# oresat-proto-card-Octavo.net
KiCad netlist of a schematic drawn in EAGLE
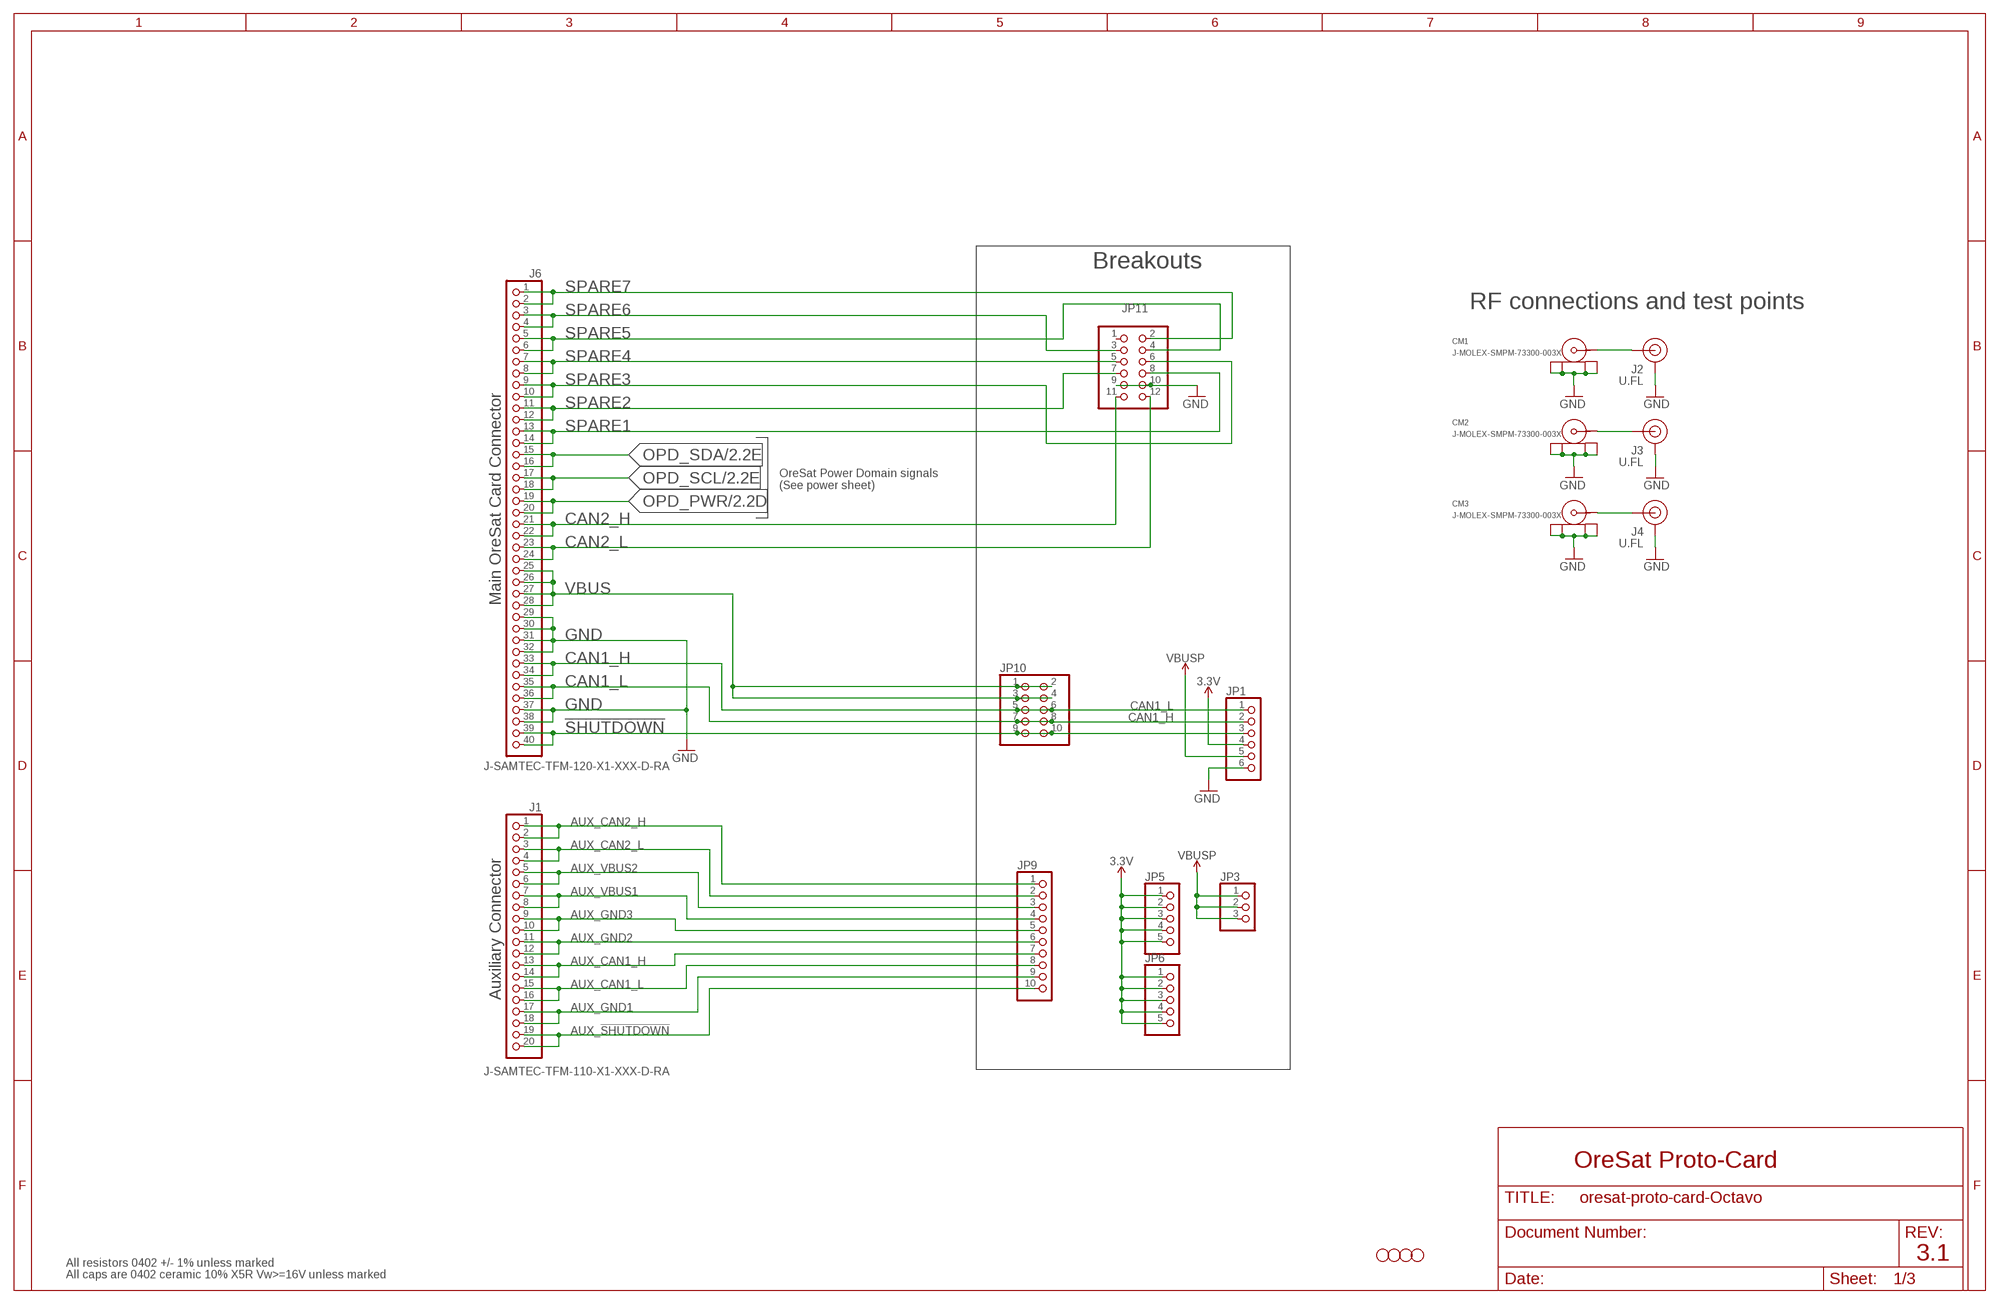
[diagram p0: schematic, sheet 1]
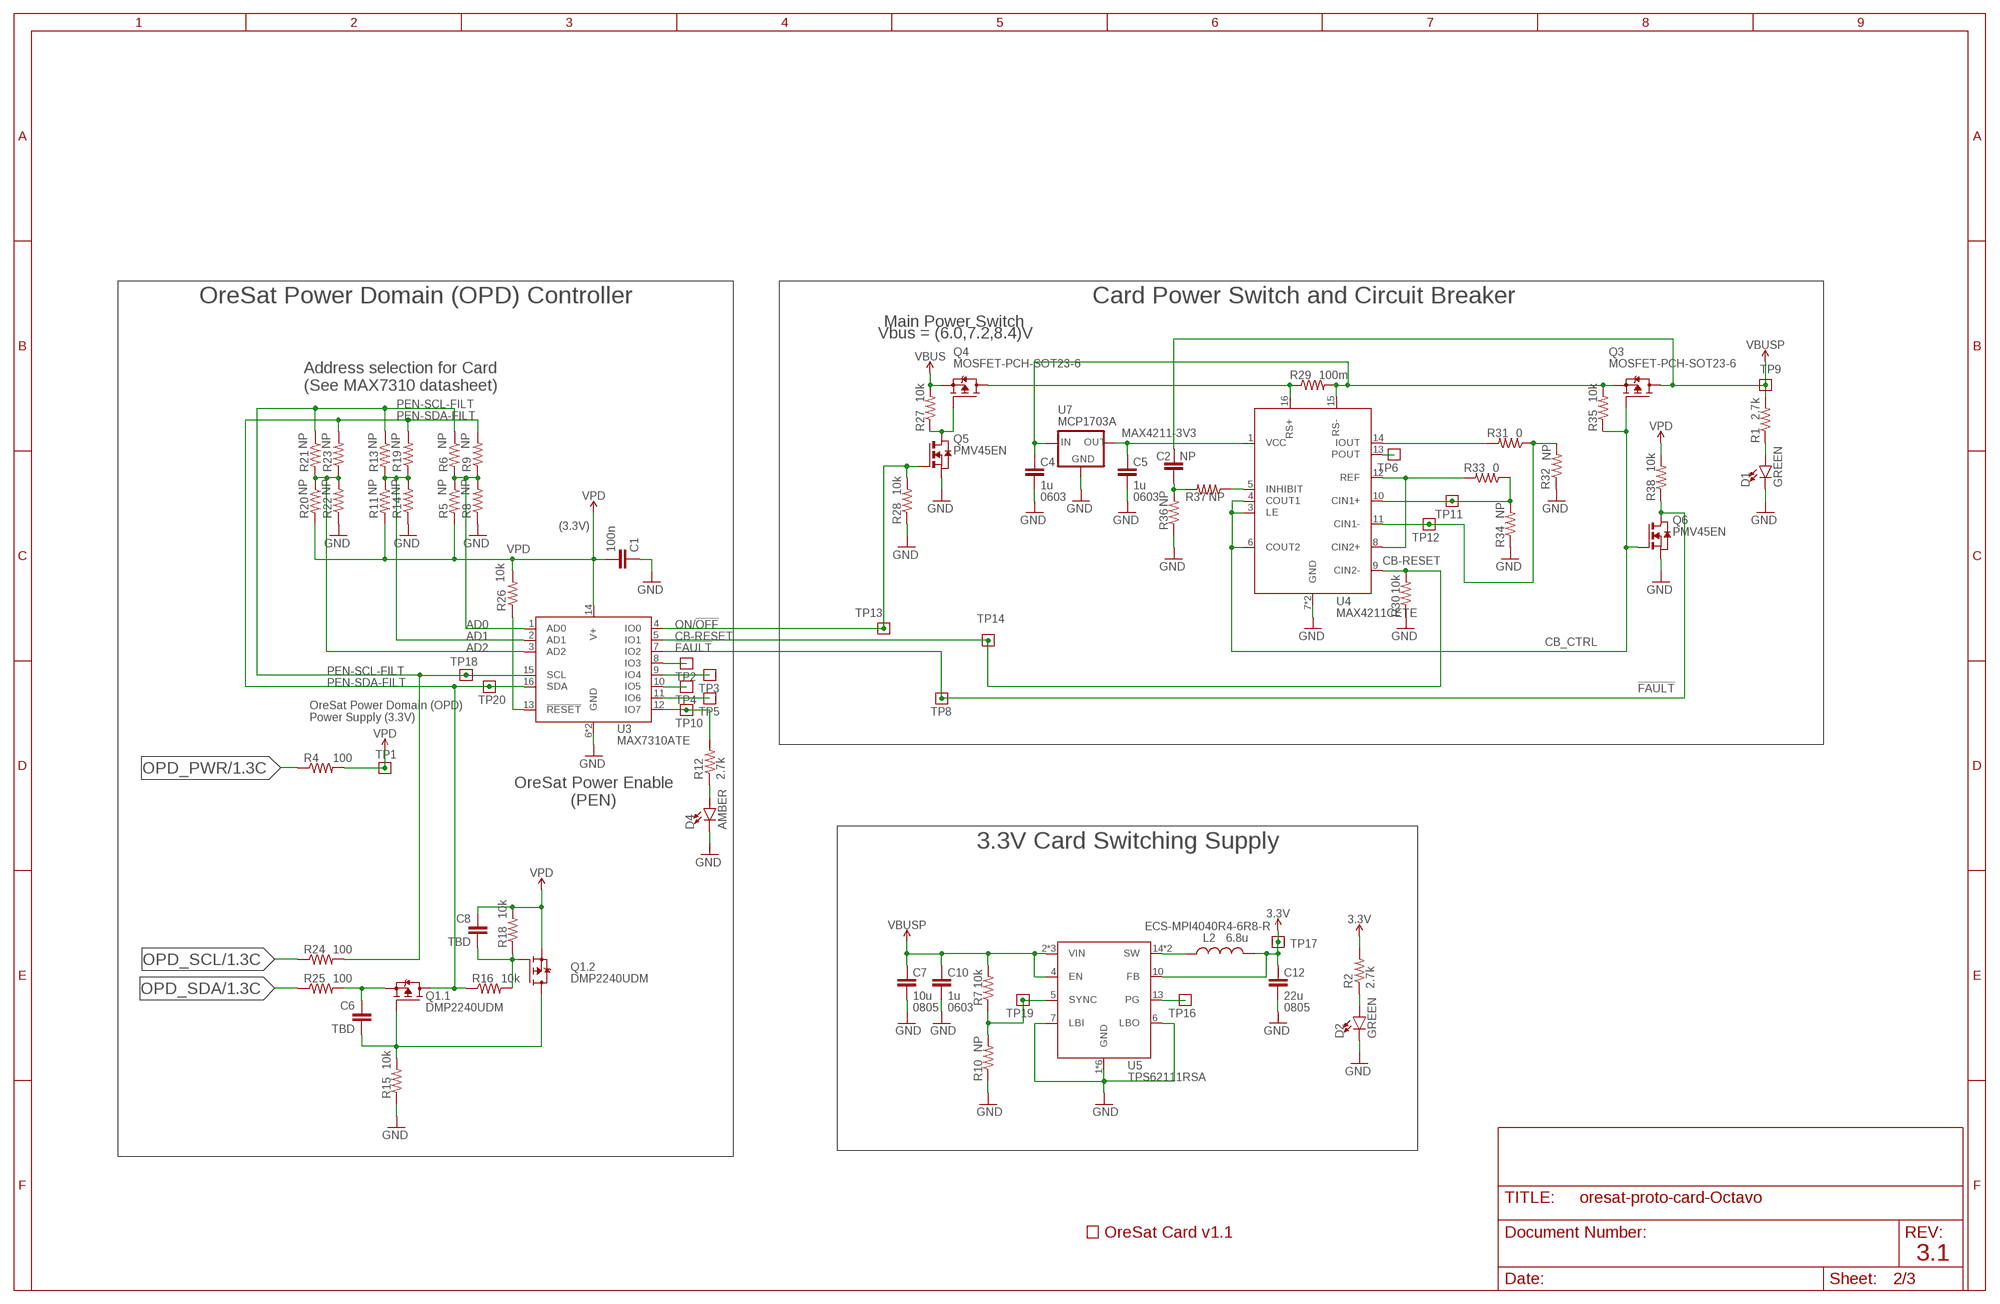
[diagram p1: schematic, sheet 2]
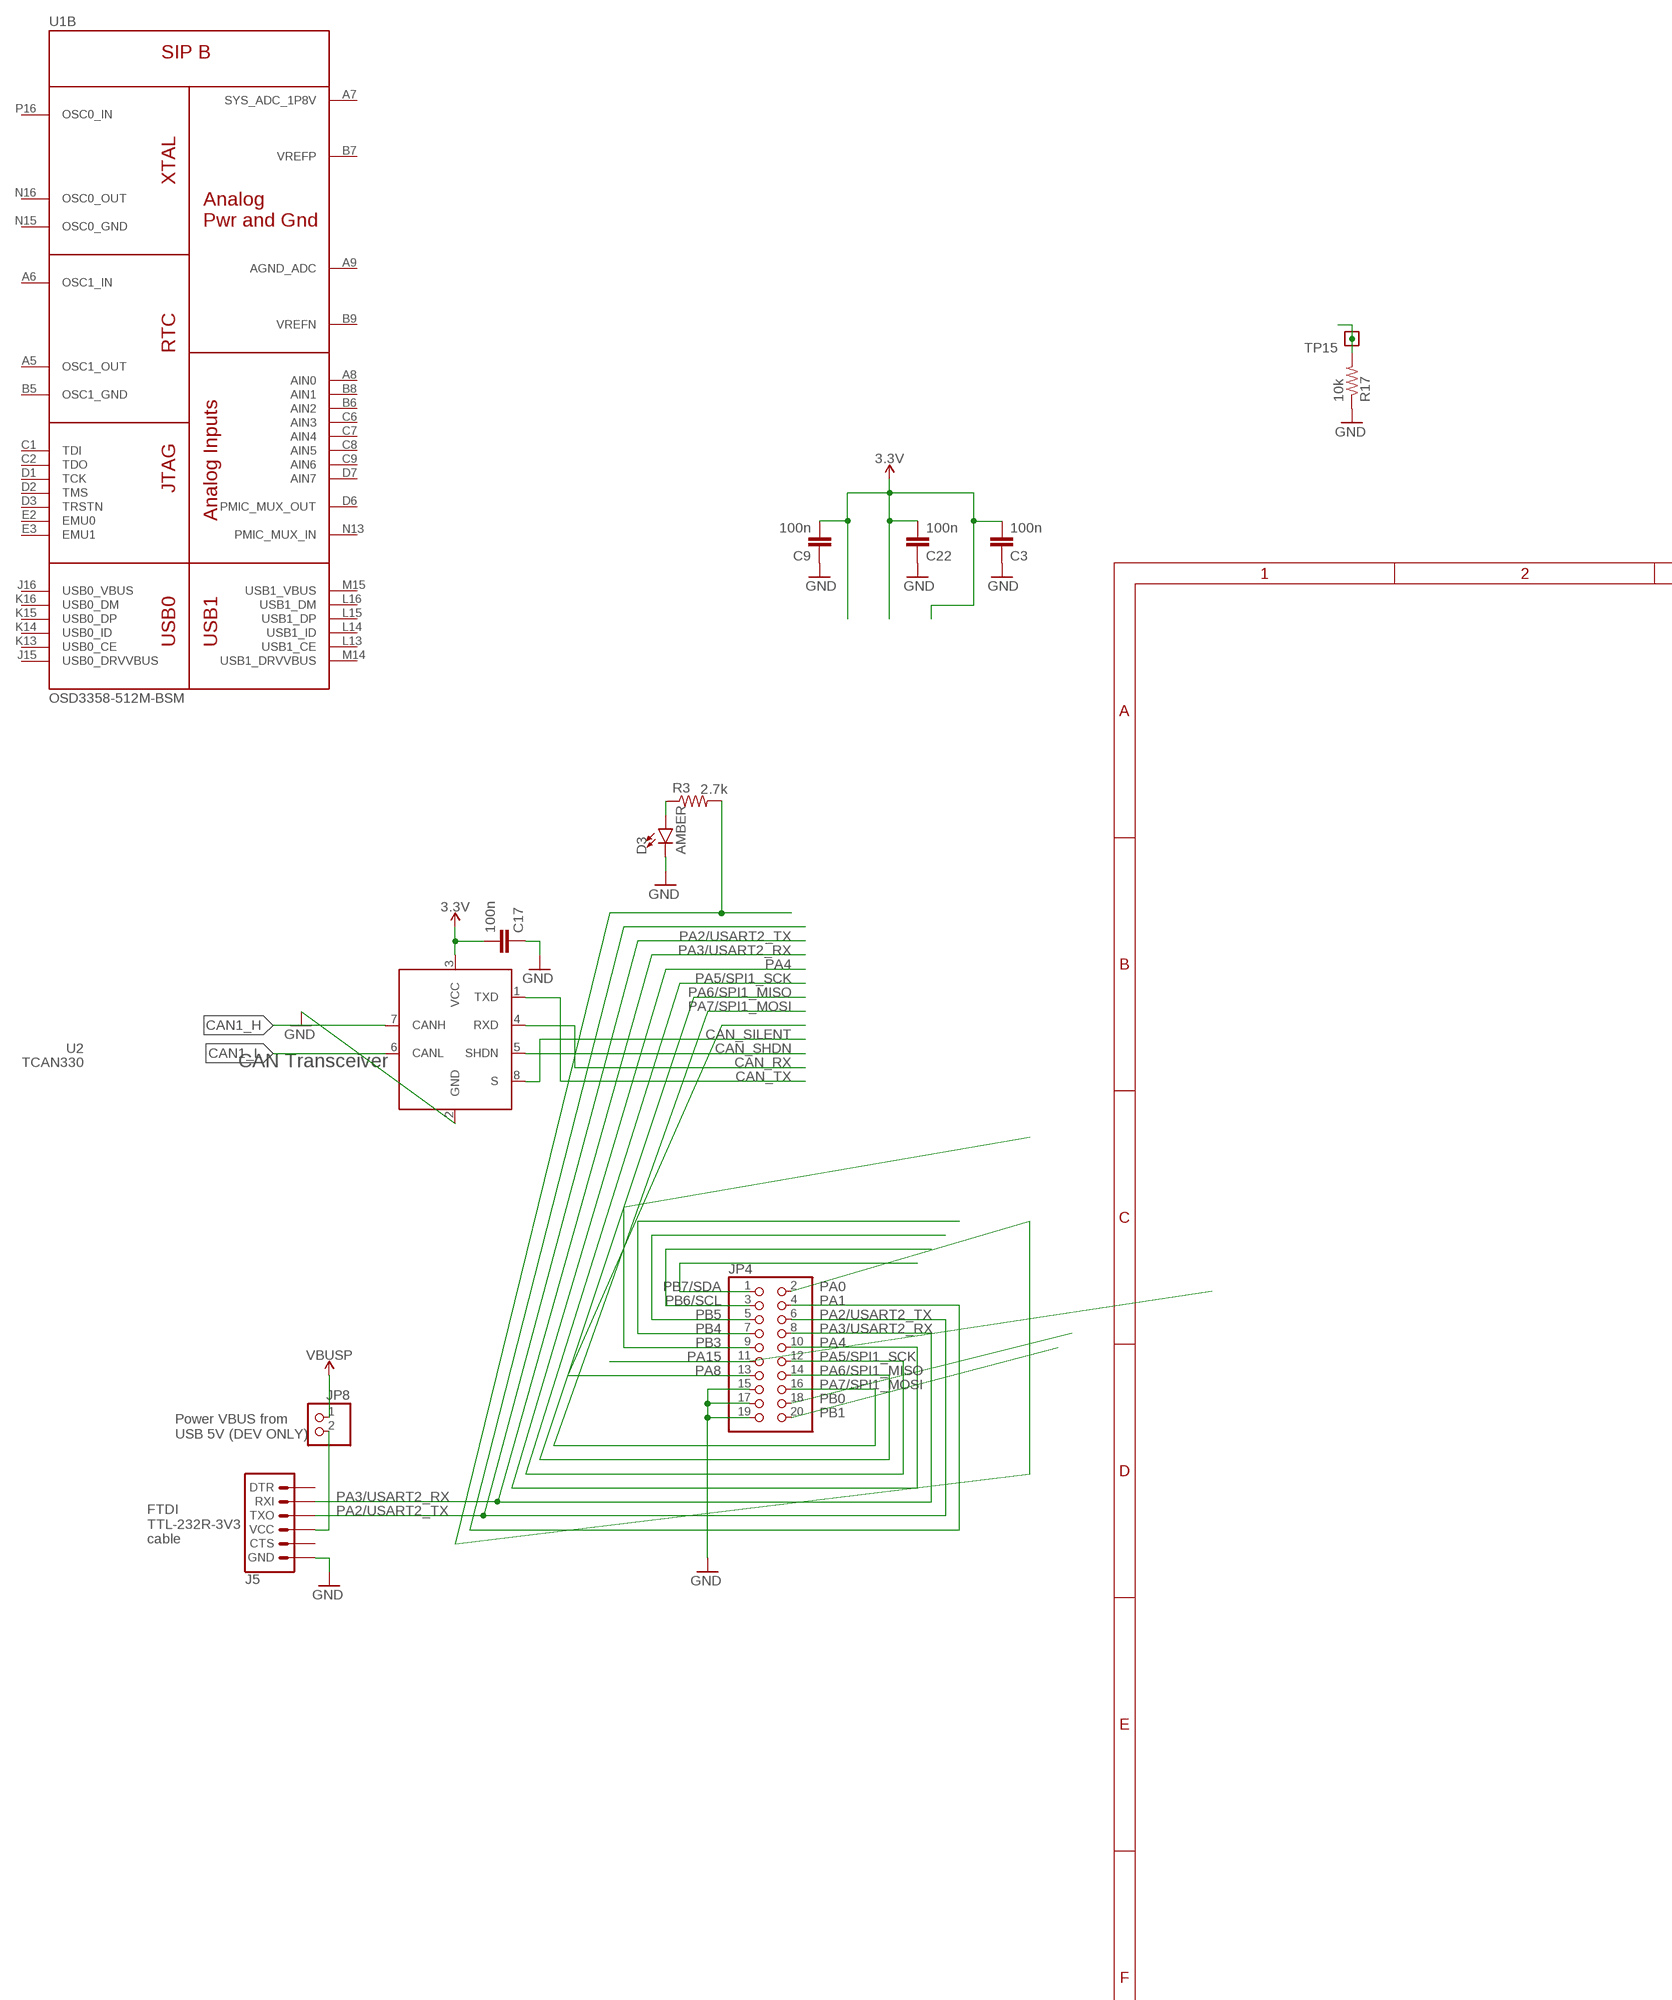
[diagram p2: schematic, sheet 3, part 1 of 2]
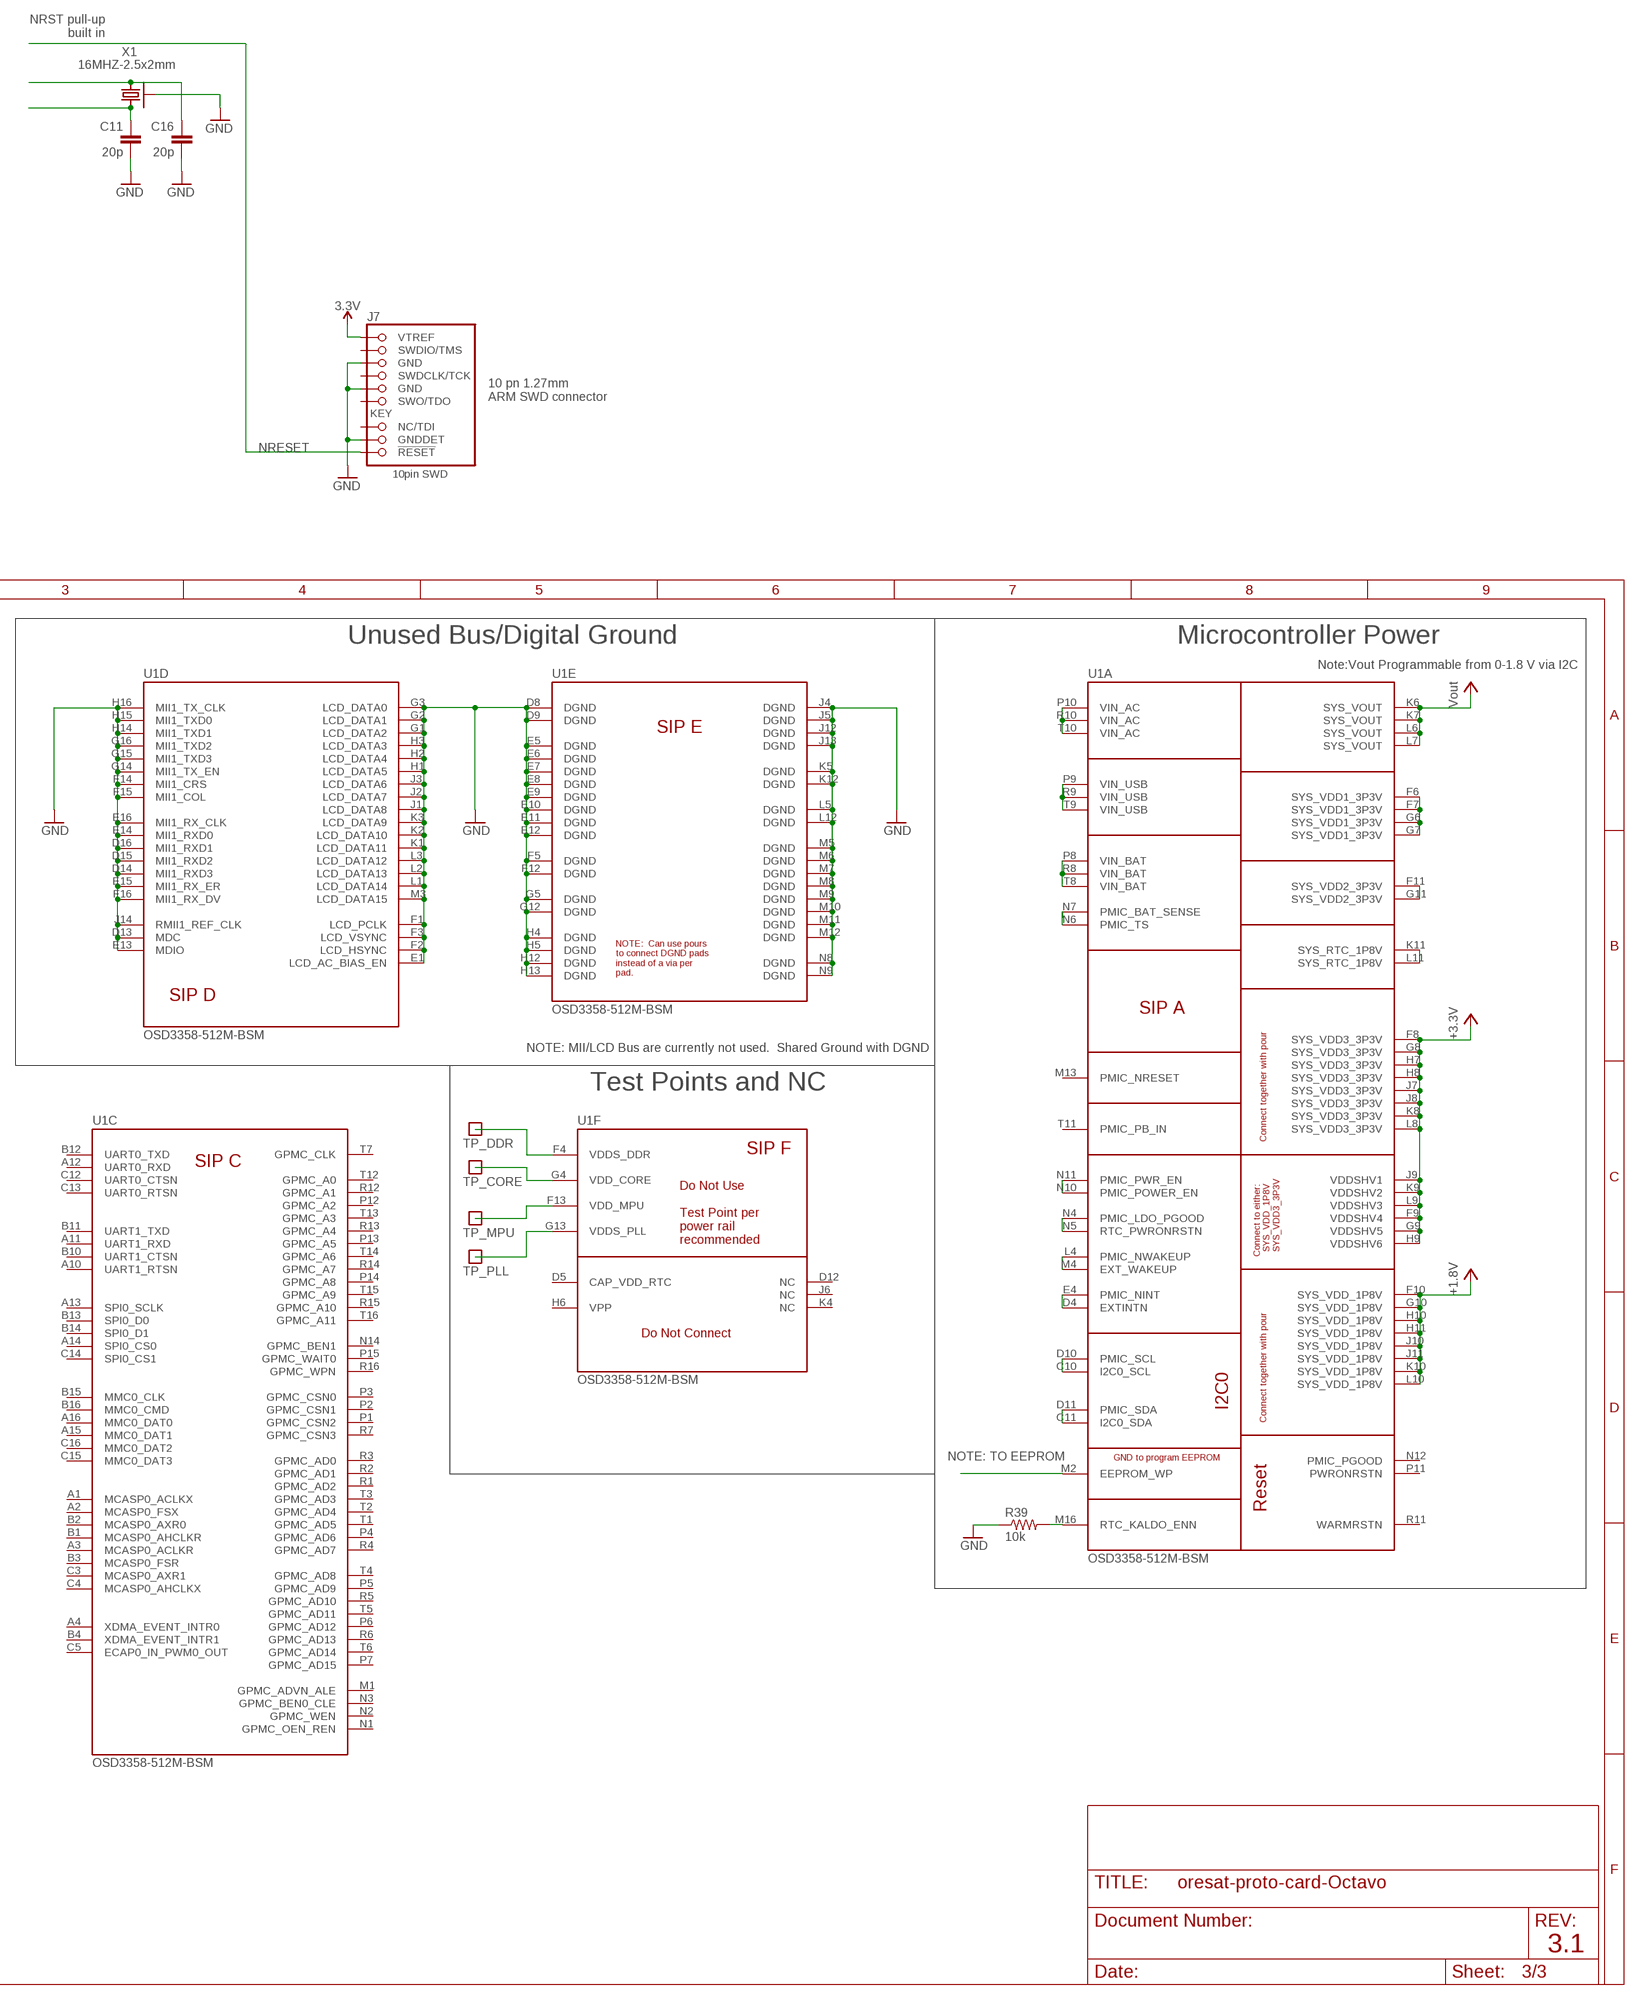
[diagram p3: schematic, sheet 3, part 2 of 2]

(export (version "E")
  (design (tool "Eeschema 10.0.6"))
  (components
    (comp (ref "C1")
      (value "100n")
      (footprint "eagle-import:.0402-B-NOSILK")
      (fields (field (name "MFR") "Samsung") (field (name "MPN") "CL05B104KO5NNNC"))
      (libsource (lib "eagle-import") (part "rcl_custom_C-EU0402-B-NOSILK"))
    )
    (comp (ref "C2")
      (value "NP")
      (footprint "eagle-import:.0402-B-NOSILK")
      (fields (field (name "MFR") "Samsung") (field (name "MPN") "CL05B104KO5NNNC"))
      (libsource (lib "eagle-import") (part "rcl_custom_C-EU0402-B-NOSILK"))
    )
    (comp (ref "C4")
      (value "1u")
      (footprint "eagle-import:.0603-B-NOSILK")
      (fields (field (name "MFR") "Samsung") (field (name "MPN") "CL05B104KO5NNNC"))
      (libsource (lib "eagle-import") (part "C-EU0603-B-NOSILK"))
    )
    (comp (ref "C5")
      (value "1u")
      (footprint "eagle-import:.0603-B-NOSILK")
      (fields (field (name "MFR") "Samsung") (field (name "MPN") "CL05B104KO5NNNC"))
      (libsource (lib "eagle-import") (part "C-EU0603-B-NOSILK"))
    )
    (comp (ref "C6")
      (value "TBD")
      (footprint "eagle-import:.0402-B-NOSILK")
      (fields (field (name "MFR") "Samsung") (field (name "MPN") "CL05B104KO5NNNC"))
      (libsource (lib "eagle-import") (part "rcl_custom_C-EU0402-B-NOSILK"))
    )
    (comp (ref "C7")
      (value "10u")
      (footprint "eagle-import:.0805-B-NOSILK")
      (libsource (lib "eagle-import") (part "C-EU0805-B-NOSILK"))
    )
    (comp (ref "C8")
      (value "TBD")
      (footprint "eagle-import:.0402-B-NOSILK")
      (fields (field (name "MFR") "Samsung") (field (name "MPN") "CL05B104KO5NNNC"))
      (libsource (lib "eagle-import") (part "rcl_custom_C-EU0402-B-NOSILK"))
    )
    (comp (ref "C10")
      (value "1u")
      (footprint "eagle-import:.0603-B-NOSILK")
      (fields (field (name "MFR") "Samsung") (field (name "MPN") "CL05B104KO5NNNC"))
      (libsource (lib "eagle-import") (part "C-EU0603-B-NOSILK"))
    )
    (comp (ref "C12")
      (value "22u")
      (footprint "eagle-import:.0805-B-NOSILK")
      (libsource (lib "eagle-import") (part "C-EU0805-B-NOSILK"))
    )
    (comp (ref "D1")
      (value "GREEN")
      (footprint "eagle-import:LED-0603")
      (libsource (lib "eagle-import") (part "LED-GREEN0603"))
    )
    (comp (ref "D2")
      (value "GREEN")
      (footprint "eagle-import:LED-0603")
      (libsource (lib "eagle-import") (part "LED-GREEN0603"))
    )
    (comp (ref "D4")
      (value "AMBER")
      (footprint "eagle-import:LED-0603")
      (libsource (lib "eagle-import") (part "LED-GREEN0603"))
    )
    (comp (ref "L2")
      (value "6.8u")
      (footprint "eagle-import:ECS-MPI4040")
      (fields (field (name "MFR") "ECS") (field (name "MPN") "ECS-MPI4040R4-6R8-R"))
      (libsource (lib "eagle-import") (part "L-ECS-MPI4040"))
    )
    (comp (ref "Q1")
      (value "DMP2240UDM")
      (footprint "eagle-import:SOT23-6")
      (fields (field (name "MFR") "Diodes Inc") (field (name "MPN") "DMP2240UDM"))
      (libsource (lib "eagle-import") (part "Q-MOSFET-PCH-dual-SOT23-6_MOSFET-PCH-SOT23-6"))
    )
    (comp (ref "Q3")
      (value "MOSFET-PCH-SOT23-6")
      (footprint "eagle-import:SOT23-6")
      (fields (field (name "MFR") "Diodes Inc") (field (name "MPN") "DMP3050LVT-7"))
      (libsource (lib "eagle-import") (part "MOSFET-PCH-SOT23-6"))
    )
    (comp (ref "Q4")
      (value "MOSFET-PCH-SOT23-6")
      (footprint "eagle-import:SOT23-6")
      (fields (field (name "MFR") "Diodes Inc") (field (name "MPN") "DMP3050LVT-7"))
      (libsource (lib "eagle-import") (part "MOSFET-PCH-SOT23-6"))
    )
    (comp (ref "Q5")
      (value "PMV45EN")
      (footprint "eagle-import:SOT23")
      (libsource (lib "eagle-import") (part "PMV45EN"))
    )
    (comp (ref "Q6")
      (value "PMV45EN")
      (footprint "eagle-import:SOT23")
      (libsource (lib "eagle-import") (part "PMV45EN"))
    )
    (comp (ref "R1")
      (value "2.7k")
      (footprint "eagle-import:.0402-B-NOSILK")
      (fields (field (name "MFR") "Samsung") (field (name "MPN") "RC1005F6653CS"))
      (libsource (lib "eagle-import") (part "R-US_0402-B-NOSILK"))
    )
    (comp (ref "R2")
      (value "2.7k")
      (footprint "eagle-import:.0402-B-NOSILK")
      (fields (field (name "MFR") "Samsung") (field (name "MPN") "RC1005F6653CS"))
      (libsource (lib "eagle-import") (part "R-US_0402-B-NOSILK"))
    )
    (comp (ref "R4")
      (value "100")
      (footprint "eagle-import:.0402-B-NOSILK")
      (fields (field (name "MFR") "Samsung") (field (name "MPN") "RC1005F6653CS"))
      (libsource (lib "eagle-import") (part "R-US_0402-B-NOSILK"))
    )
    (comp (ref "R5")
      (value "NP")
      (footprint "eagle-import:.0402-B-NOSILK")
      (fields (field (name "MFR") "Samsung") (field (name "MPN") "RC1005F6653CS"))
      (libsource (lib "eagle-import") (part "R-US_0402-B-NOSILK"))
    )
    (comp (ref "R6")
      (value "NP")
      (footprint "eagle-import:.0402-B-NOSILK")
      (fields (field (name "MFR") "Samsung") (field (name "MPN") "RC1005F6653CS"))
      (libsource (lib "eagle-import") (part "R-US_0402-B-NOSILK"))
    )
    (comp (ref "R7")
      (value "10k")
      (footprint "eagle-import:.0402-B-NOSILK")
      (fields (field (name "MFR") "Samsung") (field (name "MPN") "RC1005F6653CS"))
      (libsource (lib "eagle-import") (part "R-US_0402-B-NOSILK"))
    )
    (comp (ref "R8")
      (value "NP")
      (footprint "eagle-import:.0402-B-NOSILK")
      (fields (field (name "MFR") "Samsung") (field (name "MPN") "RC1005F6653CS"))
      (libsource (lib "eagle-import") (part "R-US_0402-B-NOSILK"))
    )
    (comp (ref "R9")
      (value "NP")
      (footprint "eagle-import:.0402-B-NOSILK")
      (fields (field (name "MFR") "Samsung") (field (name "MPN") "RC1005F6653CS"))
      (libsource (lib "eagle-import") (part "R-US_0402-B-NOSILK"))
    )
    (comp (ref "R10")
      (value "NP")
      (footprint "eagle-import:.0402-B-NOSILK")
      (fields (field (name "MFR") "Samsung") (field (name "MPN") "RC1005F6653CS"))
      (libsource (lib "eagle-import") (part "R-US_0402-B-NOSILK"))
    )
    (comp (ref "R11")
      (value "NP")
      (footprint "eagle-import:.0402-B-NOSILK")
      (fields (field (name "MFR") "Samsung") (field (name "MPN") "RC1005F6653CS"))
      (libsource (lib "eagle-import") (part "R-US_0402-B-NOSILK"))
    )
    (comp (ref "R12")
      (value "2.7k")
      (footprint "eagle-import:.0402-B-NOSILK")
      (fields (field (name "MFR") "Samsung") (field (name "MPN") "RC1005F6653CS"))
      (libsource (lib "eagle-import") (part "R-US_0402-B-NOSILK"))
    )
    (comp (ref "R13")
      (value "NP")
      (footprint "eagle-import:.0402-B-NOSILK")
      (fields (field (name "MFR") "Samsung") (field (name "MPN") "RC1005F6653CS"))
      (libsource (lib "eagle-import") (part "R-US_0402-B-NOSILK"))
    )
    (comp (ref "R14")
      (value "NP")
      (footprint "eagle-import:.0402-B-NOSILK")
      (fields (field (name "MFR") "Samsung") (field (name "MPN") "RC1005F6653CS"))
      (libsource (lib "eagle-import") (part "R-US_0402-B-NOSILK"))
    )
    (comp (ref "R15")
      (value "10k")
      (footprint "eagle-import:.0402-B-NOSILK")
      (fields (field (name "MFR") "Samsung") (field (name "MPN") "RC1005F6653CS"))
      (libsource (lib "eagle-import") (part "R-US_0402-B-NOSILK"))
    )
    (comp (ref "R16")
      (value "10k")
      (footprint "eagle-import:.0402-B-NOSILK")
      (fields (field (name "MFR") "Samsung") (field (name "MPN") "RC1005F6653CS"))
      (libsource (lib "eagle-import") (part "R-US_0402-B-NOSILK"))
    )
    (comp (ref "R18")
      (value "10k")
      (footprint "eagle-import:.0402-B-NOSILK")
      (fields (field (name "MFR") "Samsung") (field (name "MPN") "RC1005F6653CS"))
      (libsource (lib "eagle-import") (part "R-US_0402-B-NOSILK"))
    )
    (comp (ref "R19")
      (value "NP")
      (footprint "eagle-import:.0402-B-NOSILK")
      (fields (field (name "MFR") "Samsung") (field (name "MPN") "RC1005F6653CS"))
      (libsource (lib "eagle-import") (part "R-US_0402-B-NOSILK"))
    )
    (comp (ref "R20")
      (value "NP")
      (footprint "eagle-import:.0402-B-NOSILK")
      (fields (field (name "MFR") "Samsung") (field (name "MPN") "RC1005F6653CS"))
      (libsource (lib "eagle-import") (part "R-US_0402-B-NOSILK"))
    )
    (comp (ref "R21")
      (value "NP")
      (footprint "eagle-import:.0402-B-NOSILK")
      (fields (field (name "MFR") "Samsung") (field (name "MPN") "RC1005F6653CS"))
      (libsource (lib "eagle-import") (part "R-US_0402-B-NOSILK"))
    )
    (comp (ref "R22")
      (value "NP")
      (footprint "eagle-import:.0402-B-NOSILK")
      (fields (field (name "MFR") "Samsung") (field (name "MPN") "RC1005F6653CS"))
      (libsource (lib "eagle-import") (part "R-US_0402-B-NOSILK"))
    )
    (comp (ref "R23")
      (value "NP")
      (footprint "eagle-import:.0402-B-NOSILK")
      (fields (field (name "MFR") "Samsung") (field (name "MPN") "RC1005F6653CS"))
      (libsource (lib "eagle-import") (part "R-US_0402-B-NOSILK"))
    )
    (comp (ref "R24")
      (value "100")
      (footprint "eagle-import:.0402-B-NOSILK")
      (fields (field (name "MFR") "Samsung") (field (name "MPN") "RC1005F6653CS"))
      (libsource (lib "eagle-import") (part "R-US_0402-B-NOSILK"))
    )
    (comp (ref "R25")
      (value "100")
      (footprint "eagle-import:.0402-B-NOSILK")
      (fields (field (name "MFR") "Samsung") (field (name "MPN") "RC1005F6653CS"))
      (libsource (lib "eagle-import") (part "R-US_0402-B-NOSILK"))
    )
    (comp (ref "R26")
      (value "10k")
      (footprint "eagle-import:.0402-B-NOSILK")
      (fields (field (name "MFR") "Samsung") (field (name "MPN") "RC1005F6653CS"))
      (libsource (lib "eagle-import") (part "R-US_0402-B-NOSILK"))
    )
    (comp (ref "R27")
      (value "10k")
      (footprint "eagle-import:.0402-B-NOSILK")
      (fields (field (name "MFR") "Samsung") (field (name "MPN") "RC1005F6653CS"))
      (libsource (lib "eagle-import") (part "R-US_0402-B-NOSILK"))
    )
    (comp (ref "R28")
      (value "10k")
      (footprint "eagle-import:.0402-B-NOSILK")
      (fields (field (name "MFR") "Samsung") (field (name "MPN") "RC1005F6653CS"))
      (libsource (lib "eagle-import") (part "R-US_0402-B-NOSILK"))
    )
    (comp (ref "R29")
      (value "100m")
      (footprint "eagle-import:R1206")
      (libsource (lib "eagle-import") (part "R-US_R1206"))
    )
    (comp (ref "R30")
      (value "10k")
      (footprint "eagle-import:.0402-B-NOSILK")
      (fields (field (name "MFR") "Samsung") (field (name "MPN") "RC1005F6653CS"))
      (libsource (lib "eagle-import") (part "R-US_0402-B-NOSILK"))
    )
    (comp (ref "R31")
      (value "0")
      (footprint "eagle-import:.0402-B-NOSILK")
      (fields (field (name "MFR") "Samsung") (field (name "MPN") "RC1005F6653CS"))
      (libsource (lib "eagle-import") (part "R-US_0402-B-NOSILK"))
    )
    (comp (ref "R32")
      (value "NP")
      (footprint "eagle-import:.0402-B-NOSILK")
      (fields (field (name "MFR") "Samsung") (field (name "MPN") "RC1005F6653CS"))
      (libsource (lib "eagle-import") (part "R-US_0402-B-NOSILK"))
    )
    (comp (ref "R33")
      (value "0")
      (footprint "eagle-import:.0402-B-NOSILK")
      (fields (field (name "MFR") "Samsung") (field (name "MPN") "RC1005F6653CS"))
      (libsource (lib "eagle-import") (part "R-US_0402-B-NOSILK"))
    )
    (comp (ref "R34")
      (value "NP")
      (footprint "eagle-import:.0402-B-NOSILK")
      (fields (field (name "MFR") "Samsung") (field (name "MPN") "RC1005F6653CS"))
      (libsource (lib "eagle-import") (part "R-US_0402-B-NOSILK"))
    )
    (comp (ref "R35")
      (value "10k")
      (footprint "eagle-import:.0402-B-NOSILK")
      (fields (field (name "MFR") "Samsung") (field (name "MPN") "RC1005F6653CS"))
      (libsource (lib "eagle-import") (part "R-US_0402-B-NOSILK"))
    )
    (comp (ref "R36")
      (value "NP")
      (footprint "eagle-import:.0402-B-NOSILK")
      (fields (field (name "MFR") "Samsung") (field (name "MPN") "RC1005F6653CS"))
      (libsource (lib "eagle-import") (part "R-US_0402-B-NOSILK"))
    )
    (comp (ref "R37")
      (value "NP")
      (footprint "eagle-import:.0402-B-NOSILK")
      (fields (field (name "MFR") "Samsung") (field (name "MPN") "RC1005F6653CS"))
      (libsource (lib "eagle-import") (part "R-US_0402-B-NOSILK"))
    )
    (comp (ref "R38")
      (value "10k")
      (footprint "eagle-import:.0402-B-NOSILK")
      (fields (field (name "MFR") "Samsung") (field (name "MPN") "RC1005F6653CS"))
      (libsource (lib "eagle-import") (part "R-US_0402-B-NOSILK"))
    )
    (comp (ref "TP1")
      (value "TEST-POINT")
      (footprint "eagle-import:2MM-TEST-POINT")
      (libsource (lib "eagle-import") (part "TEST-POINT"))
    )
    (comp (ref "TP2")
      (value "TEST-POINT")
      (footprint "eagle-import:2MM-TEST-POINT")
      (libsource (lib "eagle-import") (part "TEST-POINT"))
    )
    (comp (ref "TP3")
      (value "TEST-POINT")
      (footprint "eagle-import:2MM-TEST-POINT")
      (libsource (lib "eagle-import") (part "TEST-POINT"))
    )
    (comp (ref "TP4")
      (value "TEST-POINT")
      (footprint "eagle-import:2MM-TEST-POINT")
      (libsource (lib "eagle-import") (part "TEST-POINT"))
    )
    (comp (ref "TP5")
      (value "TEST-POINT")
      (footprint "eagle-import:2MM-TEST-POINT")
      (libsource (lib "eagle-import") (part "TEST-POINT"))
    )
    (comp (ref "TP6")
      (value "TEST-POINT")
      (footprint "eagle-import:2MM-TEST-POINT")
      (libsource (lib "eagle-import") (part "TEST-POINT"))
    )
    (comp (ref "TP8")
      (value "TEST-POINT")
      (footprint "eagle-import:2MM-TEST-POINT")
      (libsource (lib "eagle-import") (part "TEST-POINT"))
    )
    (comp (ref "TP9")
      (value "TEST-POINT")
      (footprint "eagle-import:2MM-TEST-POINT")
      (libsource (lib "eagle-import") (part "TEST-POINT"))
    )
    (comp (ref "TP10")
      (value "TEST-POINT")
      (footprint "eagle-import:2MM-TEST-POINT")
      (libsource (lib "eagle-import") (part "TEST-POINT"))
    )
    (comp (ref "TP11")
      (value "TEST-POINT")
      (footprint "eagle-import:2MM-TEST-POINT")
      (libsource (lib "eagle-import") (part "TEST-POINT"))
    )
    (comp (ref "TP12")
      (value "TEST-POINT")
      (footprint "eagle-import:2MM-TEST-POINT")
      (libsource (lib "eagle-import") (part "TEST-POINT"))
    )
    (comp (ref "TP13")
      (value "TEST-POINT")
      (footprint "eagle-import:2MM-TEST-POINT")
      (libsource (lib "eagle-import") (part "TEST-POINT"))
    )
    (comp (ref "TP14")
      (value "TEST-POINT")
      (footprint "eagle-import:2MM-TEST-POINT")
      (libsource (lib "eagle-import") (part "TEST-POINT"))
    )
    (comp (ref "TP16")
      (value "TEST-POINT")
      (footprint "eagle-import:2MM-TEST-POINT")
      (libsource (lib "eagle-import") (part "TEST-POINT"))
    )
    (comp (ref "TP17")
      (value "TEST-POINT")
      (footprint "eagle-import:2MM-TEST-POINT")
      (libsource (lib "eagle-import") (part "TEST-POINT"))
    )
    (comp (ref "TP18")
      (value "TEST-POINT")
      (footprint "eagle-import:2MM-TEST-POINT")
      (libsource (lib "eagle-import") (part "TEST-POINT"))
    )
    (comp (ref "TP19")
      (value "TEST-POINT")
      (footprint "eagle-import:2MM-TEST-POINT")
      (libsource (lib "eagle-import") (part "TEST-POINT"))
    )
    (comp (ref "TP20")
      (value "TEST-POINT")
      (footprint "eagle-import:2MM-TEST-POINT")
      (libsource (lib "eagle-import") (part "TEST-POINT"))
    )
    (comp (ref "U$1")
      (value "ORESAT-CARD-V1.1-3XRF")
      (footprint "eagle-import:ORESAT-CARD-V1.1-3XRF")
      (libsource (lib "eagle-import") (part "ORESAT-CARD-V1.1-3XRF"))
    )
    (comp (ref "U3")
      (value "MAX7310ATE")
      (footprint "eagle-import:QFN65P400X400X80-17T210")
      (fields (field (name "MFR") "Maxim"))
      (libsource (lib "eagle-import") (part "MAX7310"))
    )
    (comp (ref "U4")
      (value "MAX4211CETE")
      (footprint "eagle-import:QFN65P400X400X80-17T210")
      (fields (field (name "MFR") "Maxim"))
      (libsource (lib "eagle-import") (part "MAX4211"))
    )
    (comp (ref "U5")
      (value "TPS62111RSA")
      (footprint "eagle-import:S-PVQFN-16")
      (fields (field (name "MFR") "TI"))
      (libsource (lib "eagle-import") (part "TPS6211X"))
    )
    (comp (ref "U7")
      (value "MCP1703A")
      (footprint "eagle-import:SOT23")
      (fields (field (name "MFR") "Microchip") (field (name "MPN") "MCP1703AT-3302E/CB"))
      (libsource (lib "eagle-import") (part "XC63FPM"))
    )
    (comp (ref "C3")
      (value "100n")
      (footprint "eagle-import:.0402-B-NOSILK")
      (fields (field (name "MFR") "Samsung") (field (name "MPN") "CL05B104KO5NNNC"))
      (libsource (lib "eagle-import") (part "rcl_custom_C-EU0402-B-NOSILK"))
    )
    (comp (ref "C9")
      (value "100n")
      (footprint "eagle-import:.0402-B-NOSILK")
      (fields (field (name "MFR") "Samsung") (field (name "MPN") "CL05B104KO5NNNC"))
      (libsource (lib "eagle-import") (part "rcl_custom_C-EU0402-B-NOSILK"))
    )
    (comp (ref "C11")
      (value "20p")
      (footprint "eagle-import:.0402-B-NOSILK")
      (fields (field (name "MFR") "Samsung") (field (name "MPN") "CL05C200JB51PNC"))
      (libsource (lib "eagle-import") (part "rcl_custom_C-EU0402-B-NOSILK"))
    )
    (comp (ref "C16")
      (value "20p")
      (footprint "eagle-import:.0402-B-NOSILK")
      (fields (field (name "MFR") "Samsung") (field (name "MPN") "CL05C200JB51PNC"))
      (libsource (lib "eagle-import") (part "rcl_custom_C-EU0402-B-NOSILK"))
    )
    (comp (ref "C17")
      (value "100n")
      (footprint "eagle-import:.0402-B-NOSILK")
      (fields (field (name "MFR") "Samsung") (field (name "MPN") "CL05B104KO5NNNC"))
      (libsource (lib "eagle-import") (part "rcl_custom_C-EU0402-B-NOSILK"))
    )
    (comp (ref "C22")
      (value "100n")
      (footprint "eagle-import:.0402-B-NOSILK")
      (fields (field (name "MFR") "Samsung") (field (name "MPN") "CL05B104KO5NNNC"))
      (libsource (lib "eagle-import") (part "rcl_custom_C-EU0402-B-NOSILK"))
    )
    (comp (ref "D3")
      (value "AMBER")
      (footprint "eagle-import:LED-0603")
      (libsource (lib "eagle-import") (part "LED-GREEN0603"))
    )
    (comp (ref "J5")
      (value "6_PIN_SERIAL_TARGETSILK")
      (footprint "eagle-import:6_PIN_SERIAL_TARGET_SIDE_W_SILK")
      (libsource (lib "eagle-import") (part "6_PIN_SERIAL_TARGETSILK"))
    )
    (comp (ref "J7")
      (value "FTSH-105-XX-X-DV-K")
      (footprint "eagle-import:CON10_2X5_DUK_FTSH")
      (fields (field (name "MFR") "Samtec") (field (name "MPN") "FTSH-105-01-F-DV-K"))
      (libsource (lib "eagle-import") (part "FTSH-105-XX-X-DV-K"))
    )
    (comp (ref "JP4")
      (value "PINHD-2X10")
      (footprint "eagle-import:2X10")
      (libsource (lib "eagle-import") (part "PINHD-2X10"))
    )
    (comp (ref "JP8")
      (value "PINHD-1X2")
      (footprint "eagle-import:1X02")
      (libsource (lib "eagle-import") (part "PINHD-1X2"))
    )
    (comp (ref "R3")
      (value "2.7k")
      (footprint "eagle-import:.0402-B-NOSILK")
      (fields (field (name "MFR") "Samsung") (field (name "MPN") "RC1005F6653CS"))
      (libsource (lib "eagle-import") (part "R-US_0402-B-NOSILK"))
    )
    (comp (ref "R17")
      (value "10k")
      (footprint "eagle-import:.0402-B-NOSILK")
      (fields (field (name "MFR") "Samsung") (field (name "MPN") "RC1005F6653CS"))
      (libsource (lib "eagle-import") (part "R-US_0402-B-NOSILK"))
    )
    (comp (ref "R39")
      (value "10k")
      (footprint "eagle-import:R0201")
      (libsource (lib "eagle-import") (part "R-US_R0201"))
    )
    (comp (ref "TP15")
      (value "TEST-POINT")
      (footprint "eagle-import:2MM-TEST-POINT")
      (libsource (lib "eagle-import") (part "TEST-POINT"))
    )
    (comp (ref "TP_CORE")
      (value "TEST-POINT")
      (footprint "eagle-import:2MM-TEST-POINT")
      (libsource (lib "eagle-import") (part "TEST-POINT"))
    )
    (comp (ref "TP_DDR")
      (value "TEST-POINT")
      (footprint "eagle-import:2MM-TEST-POINT")
      (libsource (lib "eagle-import") (part "TEST-POINT"))
    )
    (comp (ref "TP_MPU")
      (value "TEST-POINT")
      (footprint "eagle-import:2MM-TEST-POINT")
      (libsource (lib "eagle-import") (part "TEST-POINT"))
    )
    (comp (ref "TP_PLL")
      (value "TEST-POINT")
      (footprint "eagle-import:2MM-TEST-POINT")
      (libsource (lib "eagle-import") (part "TEST-POINT"))
    )
    (comp (ref "U1")
      (value "OSD3358-512M-BSM")
      (footprint "eagle-import:OSD335X-BGA-256")
      (fields (field (name "DIGI-KEY_PART_NUMBER") "1676-1002-ND") (field (name "MF") "Octavo Systems"))
      (libsource (lib "eagle-import") (part "OSD3358-512M-BSM"))
    )
    (comp (ref "U2")
      (value "TCAN330")
      (footprint "eagle-import:SOT23-8_TI-DCN")
      (fields (field (name "MFR") "Texas Instruments") (field (name "MPN") "TCAN330GDCNT"))
      (libsource (lib "eagle-import") (part "TCAN330"))
    )
    (comp (ref "X1")
      (value "16MHZ-2.5x2mm")
      (footprint "eagle-import:CRYSTAL_2.5X2")
      (fields (field (name "MFR") "ECS Inc.") (field (name "MPN") "ECS-160-10-36Q-ES-TR"))
      (libsource (lib "eagle-import") (part "CRYSTAL-WITH-GND"))
    )
    (comp (ref "CM1")
      (value "J-MOLEX-SMPM-73300-003X")
      (footprint "eagle-import:J-MOLEX-SMPM-073300-003X")
      (fields (field (name "MFR") "Molex") (field (name "MPN") "73300-0020"))
      (libsource (lib "eagle-import") (part "J-MOLEX-SMPM-73300-003X"))
    )
    (comp (ref "CM2")
      (value "J-MOLEX-SMPM-73300-003X")
      (footprint "eagle-import:J-MOLEX-SMPM-073300-003X")
      (fields (field (name "MFR") "Molex") (field (name "MPN") "73300-0020"))
      (libsource (lib "eagle-import") (part "J-MOLEX-SMPM-73300-003X"))
    )
    (comp (ref "CM3")
      (value "J-MOLEX-SMPM-73300-003X")
      (footprint "eagle-import:J-MOLEX-SMPM-073300-003X")
      (fields (field (name "MFR") "Molex") (field (name "MPN") "73300-0020"))
      (libsource (lib "eagle-import") (part "J-MOLEX-SMPM-73300-003X"))
    )
    (comp (ref "H1")
      (value "STAND-OFFTIGHT")
      (footprint "eagle-import:STAND-OFF-TIGHT")
      (libsource (lib "eagle-import") (part "STAND-OFFTIGHT"))
    )
    (comp (ref "H2")
      (value "STAND-OFFTIGHT")
      (footprint "eagle-import:STAND-OFF-TIGHT")
      (libsource (lib "eagle-import") (part "STAND-OFFTIGHT"))
    )
    (comp (ref "H3")
      (value "STAND-OFFTIGHT")
      (footprint "eagle-import:STAND-OFF-TIGHT")
      (libsource (lib "eagle-import") (part "STAND-OFFTIGHT"))
    )
    (comp (ref "H4")
      (value "STAND-OFFTIGHT")
      (footprint "eagle-import:STAND-OFF-TIGHT")
      (libsource (lib "eagle-import") (part "STAND-OFFTIGHT"))
    )
    (comp (ref "J1")
      (value "J-SAMTEC-TFM-110-X1-XXX-D-RA")
      (footprint "eagle-import:J-SAMTEC-TFM-110-X1-XXX-D-RA")
      (fields (field (name "MFR") "Samtec") (field (name "MPN") "TFM-110-01-L-D-RA "))
      (libsource (lib "eagle-import") (part "J-SAMTEC-TFM-110-X1-XXX-D-RA"))
    )
    (comp (ref "J2")
      (value "U.FL")
      (footprint "eagle-import:U.FL")
      (libsource (lib "eagle-import") (part "U.FL2PIN"))
    )
    (comp (ref "J3")
      (value "U.FL")
      (footprint "eagle-import:U.FL")
      (libsource (lib "eagle-import") (part "U.FL2PIN"))
    )
    (comp (ref "J4")
      (value "U.FL")
      (footprint "eagle-import:U.FL")
      (libsource (lib "eagle-import") (part "U.FL2PIN"))
    )
    (comp (ref "J6")
      (value "J-SAMTEC-TFM-120-X1-XXX-D-RA")
      (footprint "eagle-import:J-SAMTEC-TFM-120-X1-XXX-D-RA")
      (fields (field (name "MFR") "Samtec") (field (name "MPN") "TFM-120-01-L-D-RA"))
      (libsource (lib "eagle-import") (part "J-SAMTEC-TFM-120-X1-XXX-D-RA"))
    )
    (comp (ref "JP1")
      (value "PINHD-1X6")
      (footprint "eagle-import:1X06")
      (libsource (lib "eagle-import") (part "PINHD-1X6"))
    )
    (comp (ref "JP3")
      (value "PINHD-1X3")
      (footprint "eagle-import:1X03")
      (libsource (lib "eagle-import") (part "PINHD-1X3"))
    )
    (comp (ref "JP5")
      (value "PINHD-1X5")
      (footprint "eagle-import:1X05")
      (libsource (lib "eagle-import") (part "PINHD-1X5"))
    )
    (comp (ref "JP6")
      (value "PINHD-1X5")
      (footprint "eagle-import:1X05")
      (libsource (lib "eagle-import") (part "PINHD-1X5"))
    )
    (comp (ref "JP9")
      (value "PINHD-1X10")
      (footprint "eagle-import:1X10")
      (libsource (lib "eagle-import") (part "PINHD-1X10"))
    )
    (comp (ref "JP10")
      (value "PINHD-2X5")
      (footprint "eagle-import:2X05")
      (libsource (lib "eagle-import") (part "PINHD-2X5"))
    )
    (comp (ref "JP11")
      (value "PINHD-2X6")
      (footprint "eagle-import:2X06")
      (libsource (lib "eagle-import") (part "PINHD-2X6"))
    )
  )
  (nets
    (net (code "1") (name "+3V3") (class "Default")
      (node (ref "U1") (pin "F10") (pinfunction "SYS_VDD_1P8V_F10") (pintype "power_in"))
      (node (ref "U1") (pin "F8") (pinfunction "SYS_VDD3_3P3V_F8") (pintype "power_in"))
      (node (ref "U1") (pin "F9") (pinfunction "VDDSHV4_F9") (pintype "power_in"))
      (node (ref "U1") (pin "G10") (pinfunction "SYS_VDD_1P8V_G10") (pintype "power_in"))
      (node (ref "U1") (pin "G8") (pinfunction "SYS_VDD3_3P3V_G8") (pintype "power_in"))
      (node (ref "U1") (pin "G9") (pinfunction "VDDSHV5_G9") (pintype "power_in"))
      (node (ref "U1") (pin "H10") (pinfunction "SYS_VDD_1P8V_H10") (pintype "power_in"))
      (node (ref "U1") (pin "H11") (pinfunction "SYS_VDD_1P8V_H11") (pintype "power_in"))
      (node (ref "U1") (pin "H7") (pinfunction "SYS_VDD3_3P3V_H7") (pintype "power_in"))
      (node (ref "U1") (pin "H8") (pinfunction "SYS_VDD3_3P3V_H8") (pintype "power_in"))
      (node (ref "U1") (pin "H9") (pinfunction "VDDSHV6_H9") (pintype "power_in"))
      (node (ref "U1") (pin "J10") (pinfunction "SYS_VDD_1P8V_J10") (pintype "power_in"))
      (node (ref "U1") (pin "J11") (pinfunction "SYS_VDD_1P8V_J11") (pintype "power_in"))
      (node (ref "U1") (pin "J7") (pinfunction "SYS_VDD3_3P3V_J7") (pintype "power_in"))
      (node (ref "U1") (pin "J8") (pinfunction "SYS_VDD3_3P3V_J8") (pintype "power_in"))
      (node (ref "U1") (pin "J9") (pinfunction "VDDSHV1_J9") (pintype "power_in"))
      (node (ref "U1") (pin "K10") (pinfunction "SYS_VDD_1P8V_K10") (pintype "power_in"))
      (node (ref "U1") (pin "K8") (pinfunction "SYS_VDD3_3P3V_K8") (pintype "power_in"))
      (node (ref "U1") (pin "K9") (pinfunction "VDDSHV2_K9") (pintype "power_in"))
      (node (ref "U1") (pin "L10") (pinfunction "SYS_VDD_1P8V_L10") (pintype "power_in"))
      (node (ref "U1") (pin "L8") (pinfunction "SYS_VDD3_3P3V_L8") (pintype "power_in"))
      (node (ref "U1") (pin "L9") (pinfunction "VDDSHV3_L9") (pintype "power_in"))
    )
    (net (code "2") (name "3.3V") (class "Default")
      (node (ref "C12") (pin "1") (pinfunction "1_1") (pintype "passive"))
      (node (ref "C17") (pin "2") (pinfunction "2_2") (pintype "passive"))
      (node (ref "C22") (pin "2") (pinfunction "2_2") (pintype "passive"))
      (node (ref "C3") (pin "2") (pinfunction "2_2") (pintype "passive"))
      (node (ref "C9") (pin "2") (pinfunction "2_2") (pintype "passive"))
      (node (ref "J7") (pin "1") (pinfunction "VTREF_1") (pintype "passive"))
      (node (ref "JP1") (pin "4") (pinfunction "4_4") (pintype "passive"))
      (node (ref "JP5") (pin "1") (pinfunction "1_1") (pintype "passive"))
      (node (ref "JP5") (pin "2") (pinfunction "2_2") (pintype "passive"))
      (node (ref "JP5") (pin "3") (pinfunction "3_3") (pintype "passive"))
      (node (ref "JP5") (pin "4") (pinfunction "4_4") (pintype "passive"))
      (node (ref "JP5") (pin "5") (pinfunction "5_5") (pintype "passive"))
      (node (ref "JP6") (pin "1") (pinfunction "1_1") (pintype "passive"))
      (node (ref "JP6") (pin "2") (pinfunction "2_2") (pintype "passive"))
      (node (ref "JP6") (pin "3") (pinfunction "3_3") (pintype "passive"))
      (node (ref "JP6") (pin "4") (pinfunction "4_4") (pintype "passive"))
      (node (ref "JP6") (pin "5") (pinfunction "5_5") (pintype "passive"))
      (node (ref "L2") (pin "2") (pinfunction "2_2") (pintype "passive"))
      (node (ref "R2") (pin "2") (pinfunction "2_2") (pintype "passive"))
      (node (ref "TP17") (pin "1") (pinfunction "1_1") (pintype "passive"))
      (node (ref "U2") (pin "3") (pinfunction "VCC_3") (pintype "power_in"))
      (node (ref "U5") (pin "10") (pinfunction "FB_10") (pintype "input"))
    )
    (net (code "3") (name "AD0") (class "Default")
      (node (ref "R5") (pin "1") (pinfunction "1_1") (pintype "passive"))
      (node (ref "R6") (pin "2") (pinfunction "2_2") (pintype "passive"))
      (node (ref "R8") (pin "2") (pinfunction "2_2") (pintype "passive"))
      (node (ref "R9") (pin "1") (pinfunction "1_1") (pintype "passive"))
      (node (ref "U3") (pin "1") (pinfunction "AD0_1") (pintype "input"))
    )
    (net (code "4") (name "AD1") (class "Default")
      (node (ref "R11") (pin "1") (pinfunction "1_1") (pintype "passive"))
      (node (ref "R13") (pin "2") (pinfunction "2_2") (pintype "passive"))
      (node (ref "R14") (pin "2") (pinfunction "2_2") (pintype "passive"))
      (node (ref "R19") (pin "1") (pinfunction "1_1") (pintype "passive"))
      (node (ref "U3") (pin "2") (pinfunction "AD1_2") (pintype "input"))
    )
    (net (code "5") (name "AD2") (class "Default")
      (node (ref "R20") (pin "1") (pinfunction "1_1") (pintype "passive"))
      (node (ref "R21") (pin "2") (pinfunction "2_2") (pintype "passive"))
      (node (ref "R22") (pin "2") (pinfunction "2_2") (pintype "passive"))
      (node (ref "R23") (pin "1") (pinfunction "1_1") (pintype "passive"))
      (node (ref "U3") (pin "3") (pinfunction "AD2_3") (pintype "input"))
    )
    (net (code "6") (name "AUX_CAN1_H") (class "Default")
      (node (ref "J1") (pin "13") (pinfunction "13_13") (pintype "passive"))
      (node (ref "J1") (pin "14") (pinfunction "14_14") (pintype "passive"))
      (node (ref "JP9") (pin "7") (pinfunction "7_7") (pintype "passive"))
    )
    (net (code "7") (name "AUX_CAN1_L") (class "Default")
      (node (ref "J1") (pin "15") (pinfunction "15_15") (pintype "passive"))
      (node (ref "J1") (pin "16") (pinfunction "16_16") (pintype "passive"))
      (node (ref "JP9") (pin "8") (pinfunction "8_8") (pintype "passive"))
    )
    (net (code "8") (name "AUX_CAN2_H") (class "Default")
      (node (ref "J1") (pin "1") (pinfunction "1_1") (pintype "passive"))
      (node (ref "J1") (pin "2") (pinfunction "2_2") (pintype "passive"))
      (node (ref "JP9") (pin "1") (pinfunction "1_1") (pintype "passive"))
    )
    (net (code "9") (name "AUX_CAN2_L") (class "Default")
      (node (ref "J1") (pin "3") (pinfunction "3_3") (pintype "passive"))
      (node (ref "J1") (pin "4") (pinfunction "4_4") (pintype "passive"))
      (node (ref "JP9") (pin "2") (pinfunction "2_2") (pintype "passive"))
    )
    (net (code "10") (name "AUX_GND1") (class "Default")
      (node (ref "J1") (pin "17") (pinfunction "17_17") (pintype "passive"))
      (node (ref "J1") (pin "18") (pinfunction "18_18") (pintype "passive"))
      (node (ref "JP9") (pin "9") (pinfunction "9_9") (pintype "passive"))
    )
    (net (code "11") (name "AUX_GND2") (class "Default")
      (node (ref "J1") (pin "11") (pinfunction "11_11") (pintype "passive"))
      (node (ref "J1") (pin "12") (pinfunction "12_12") (pintype "passive"))
      (node (ref "JP9") (pin "6") (pinfunction "6_6") (pintype "passive"))
    )
    (net (code "12") (name "AUX_GND3") (class "Default")
      (node (ref "J1") (pin "10") (pinfunction "10_10") (pintype "passive"))
      (node (ref "J1") (pin "9") (pinfunction "9_9") (pintype "passive"))
      (node (ref "JP9") (pin "5") (pinfunction "5_5") (pintype "passive"))
    )
    (net (code "13") (name "AUX_VBUS1") (class "Default")
      (node (ref "J1") (pin "7") (pinfunction "7_7") (pintype "passive"))
      (node (ref "J1") (pin "8") (pinfunction "8_8") (pintype "passive"))
      (node (ref "JP9") (pin "4") (pinfunction "4_4") (pintype "passive"))
    )
    (net (code "14") (name "AUX_VBUS2") (class "Default")
      (node (ref "J1") (pin "5") (pinfunction "5_5") (pintype "passive"))
      (node (ref "J1") (pin "6") (pinfunction "6_6") (pintype "passive"))
      (node (ref "JP9") (pin "3") (pinfunction "3_3") (pintype "passive"))
    )
    (net (code "15") (name "AUX_~{SHUTDOWN}") (class "Default")
      (node (ref "J1") (pin "19") (pinfunction "19_19") (pintype "passive"))
      (node (ref "J1") (pin "20") (pinfunction "20_20") (pintype "passive"))
      (node (ref "JP9") (pin "10") (pinfunction "10_10") (pintype "passive"))
    )
    (net (code "16") (name "CAN1_H") (class "Default")
      (node (ref "J6") (pin "33") (pinfunction "33_33") (pintype "passive"))
      (node (ref "J6") (pin "34") (pinfunction "34_34") (pintype "passive"))
      (node (ref "JP1") (pin "1") (pinfunction "1_1") (pintype "passive"))
      (node (ref "JP10") (pin "5") (pinfunction "5_5") (pintype "passive"))
      (node (ref "JP10") (pin "6") (pinfunction "6_6") (pintype "passive"))
      (node (ref "U2") (pin "7") (pinfunction "CANH_7") (pintype "bidirectional"))
    )
    (net (code "17") (name "CAN1_L") (class "Default")
      (node (ref "J6") (pin "35") (pinfunction "35_35") (pintype "passive"))
      (node (ref "J6") (pin "36") (pinfunction "36_36") (pintype "passive"))
      (node (ref "JP1") (pin "2") (pinfunction "2_2") (pintype "passive"))
      (node (ref "JP10") (pin "7") (pinfunction "7_7") (pintype "passive"))
      (node (ref "JP10") (pin "8") (pinfunction "8_8") (pintype "passive"))
      (node (ref "U2") (pin "6") (pinfunction "CANL_6") (pintype "bidirectional"))
    )
    (net (code "18") (name "CAN2_H") (class "Default")
      (node (ref "J6") (pin "21") (pinfunction "21_21") (pintype "passive"))
      (node (ref "J6") (pin "22") (pinfunction "22_22") (pintype "passive"))
      (node (ref "JP11") (pin "11") (pinfunction "11_11") (pintype "passive"))
    )
    (net (code "19") (name "CAN2_L") (class "Default")
      (node (ref "J6") (pin "23") (pinfunction "23_23") (pintype "passive"))
      (node (ref "J6") (pin "24") (pinfunction "24_24") (pintype "passive"))
      (node (ref "JP11") (pin "12") (pinfunction "12_12") (pintype "passive"))
    )
    (net (code "20") (name "CAN_RX") (class "Default")
      (node (ref "U2") (pin "4") (pinfunction "RXD_4") (pintype "output"))
    )
    (net (code "21") (name "CAN_SHDN") (class "Default")
      (node (ref "U2") (pin "5") (pinfunction "SHDN_5") (pintype "input"))
    )
    (net (code "22") (name "CAN_SILENT") (class "Default")
      (node (ref "U2") (pin "8") (pinfunction "S_8") (pintype "input"))
    )
    (net (code "23") (name "CAN_TX") (class "Default")
      (node (ref "U2") (pin "1") (pinfunction "TXD_1") (pintype "input"))
    )
    (net (code "24") (name "CB-RESET") (class "Default")
      (node (ref "R30") (pin "2") (pinfunction "2_2") (pintype "passive"))
      (node (ref "TP14") (pin "1") (pinfunction "1_1") (pintype "passive"))
      (node (ref "U3") (pin "5") (pinfunction "IO1_5") (pintype "bidirectional"))
      (node (ref "U4") (pin "9") (pinfunction "CIN2-_9") (pintype "input"))
    )
    (net (code "25") (name "CB_CTRL") (class "Default")
      (node (ref "Q3") (pin "3") (pinfunction "G_3") (pintype "passive"))
      (node (ref "Q6") (pin "1") (pinfunction "G_1") (pintype "passive"))
      (node (ref "R35") (pin "1") (pinfunction "1_1") (pintype "passive"))
      (node (ref "U4") (pin "3") (pinfunction "LE_3") (pintype "input"))
      (node (ref "U4") (pin "4") (pinfunction "COUT1_4") (pintype "open_collector"))
      (node (ref "U4") (pin "6") (pinfunction "COUT2_6") (pintype "open_collector"))
    )
    (net (code "26") (name "GND") (class "Default")
      (node (ref "C1") (pin "1") (pinfunction "1_1") (pintype "passive"))
      (node (ref "C10") (pin "2") (pinfunction "2_2") (pintype "passive"))
      (node (ref "C11") (pin "2") (pinfunction "2_2") (pintype "passive"))
      (node (ref "C12") (pin "2") (pinfunction "2_2") (pintype "passive"))
      (node (ref "C16") (pin "2") (pinfunction "2_2") (pintype "passive"))
      (node (ref "C17") (pin "1") (pinfunction "1_1") (pintype "passive"))
      (node (ref "C22") (pin "1") (pinfunction "1_1") (pintype "passive"))
      (node (ref "C3") (pin "1") (pinfunction "1_1") (pintype "passive"))
      (node (ref "C4") (pin "2") (pinfunction "2_2") (pintype "passive"))
      (node (ref "C5") (pin "2") (pinfunction "2_2") (pintype "passive"))
      (node (ref "C7") (pin "2") (pinfunction "2_2") (pintype "passive"))
      (node (ref "C9") (pin "1") (pinfunction "1_1") (pintype "passive"))
      (node (ref "CM1") (pin "P$1") (pinfunction "SHIELD3_P$1") (pintype "passive"))
      (node (ref "CM1") (pin "P$2") (pinfunction "SHIELD2_P$2") (pintype "passive"))
      (node (ref "CM1") (pin "P$3") (pinfunction "SHIELD1_P$3") (pintype "passive"))
      (node (ref "CM1") (pin "P$4") (pinfunction "SHIELD_P$4") (pintype "passive"))
      (node (ref "CM2") (pin "P$1") (pinfunction "SHIELD3_P$1") (pintype "passive"))
      (node (ref "CM2") (pin "P$2") (pinfunction "SHIELD2_P$2") (pintype "passive"))
      (node (ref "CM2") (pin "P$3") (pinfunction "SHIELD1_P$3") (pintype "passive"))
      (node (ref "CM2") (pin "P$4") (pinfunction "SHIELD_P$4") (pintype "passive"))
      (node (ref "CM3") (pin "P$1") (pinfunction "SHIELD3_P$1") (pintype "passive"))
      (node (ref "CM3") (pin "P$2") (pinfunction "SHIELD2_P$2") (pintype "passive"))
      (node (ref "CM3") (pin "P$3") (pinfunction "SHIELD1_P$3") (pintype "passive"))
      (node (ref "CM3") (pin "P$4") (pinfunction "SHIELD_P$4") (pintype "passive"))
      (node (ref "D1") (pin "C") (pinfunction "C_C") (pintype "passive"))
      (node (ref "D2") (pin "C") (pinfunction "C_C") (pintype "passive"))
      (node (ref "D3") (pin "C") (pinfunction "C_C") (pintype "passive"))
      (node (ref "D4") (pin "C") (pinfunction "C_C") (pintype "passive"))
      (node (ref "J2") (pin "1") (pinfunction "GND_1") (pintype "bidirectional"))
      (node (ref "J2") (pin "2") (pinfunction "GND_2") (pintype "bidirectional"))
      (node (ref "J3") (pin "1") (pinfunction "GND_1") (pintype "bidirectional"))
      (node (ref "J3") (pin "2") (pinfunction "GND_2") (pintype "bidirectional"))
      (node (ref "J4") (pin "1") (pinfunction "GND_1") (pintype "bidirectional"))
      (node (ref "J4") (pin "2") (pinfunction "GND_2") (pintype "bidirectional"))
      (node (ref "J5") (pin "P$6") (pinfunction "GND_P$6") (pintype "passive"))
      (node (ref "J6") (pin "29") (pinfunction "29_29") (pintype "passive"))
      (node (ref "J6") (pin "30") (pinfunction "30_30") (pintype "passive"))
      (node (ref "J6") (pin "31") (pinfunction "31_31") (pintype "passive"))
      (node (ref "J6") (pin "32") (pinfunction "32_32") (pintype "passive"))
      (node (ref "J6") (pin "37") (pinfunction "37_37") (pintype "passive"))
      (node (ref "J6") (pin "38") (pinfunction "38_38") (pintype "passive"))
      (node (ref "J7") (pin "3") (pinfunction "GND_3") (pintype "passive"))
      (node (ref "J7") (pin "5") (pinfunction "GND_5") (pintype "passive"))
      (node (ref "J7") (pin "9") (pinfunction "GNDDET_9") (pintype "passive"))
      (node (ref "JP1") (pin "6") (pinfunction "6_6") (pintype "passive"))
      (node (ref "JP11") (pin "10") (pinfunction "10_10") (pintype "passive"))
      (node (ref "JP11") (pin "9") (pinfunction "9_9") (pintype "passive"))
      (node (ref "JP4") (pin "15") (pinfunction "15_15") (pintype "passive"))
      (node (ref "JP4") (pin "17") (pinfunction "17_17") (pintype "passive"))
      (node (ref "JP4") (pin "19") (pinfunction "19_19") (pintype "passive"))
      (node (ref "Q5") (pin "2") (pinfunction "S_2") (pintype "passive"))
      (node (ref "Q6") (pin "2") (pinfunction "S_2") (pintype "passive"))
      (node (ref "R10") (pin "1") (pinfunction "1_1") (pintype "passive"))
      (node (ref "R14") (pin "1") (pinfunction "1_1") (pintype "passive"))
      (node (ref "R15") (pin "1") (pinfunction "1_1") (pintype "passive"))
      (node (ref "R17") (pin "1") (pinfunction "1_1") (pintype "passive"))
      (node (ref "R22") (pin "1") (pinfunction "1_1") (pintype "passive"))
      (node (ref "R28") (pin "1") (pinfunction "1_1") (pintype "passive"))
      (node (ref "R30") (pin "1") (pinfunction "1_1") (pintype "passive"))
      (node (ref "R32") (pin "1") (pinfunction "1_1") (pintype "passive"))
      (node (ref "R34") (pin "1") (pinfunction "1_1") (pintype "passive"))
      (node (ref "R36") (pin "1") (pinfunction "1_1") (pintype "passive"))
      (node (ref "R39") (pin "1") (pinfunction "1_1") (pintype "passive"))
      (node (ref "R8") (pin "1") (pinfunction "1_1") (pintype "passive"))
      (node (ref "U1") (pin "D13") (pinfunction "MDC_D13") (pintype "bidirectional"))
      (node (ref "U1") (pin "D14") (pinfunction "MII1_RXD3_D14") (pintype "bidirectional"))
      (node (ref "U1") (pin "D15") (pinfunction "MII1_RXD2_D15") (pintype "bidirectional"))
      (node (ref "U1") (pin "D16") (pinfunction "MII1_RXD1_D16") (pintype "bidirectional"))
      (node (ref "U1") (pin "D8") (pinfunction "DGND_D8") (pintype "bidirectional"))
      (node (ref "U1") (pin "D9") (pinfunction "DGND_D9") (pintype "bidirectional"))
      (node (ref "U1") (pin "E1") (pinfunction "LCD_AC_BIAS_EN_E1") (pintype "bidirectional"))
      (node (ref "U1") (pin "E10") (pinfunction "DGND_E10") (pintype "bidirectional"))
      (node (ref "U1") (pin "E11") (pinfunction "DGND_E11") (pintype "bidirectional"))
      (node (ref "U1") (pin "E12") (pinfunction "DGND_E12") (pintype "bidirectional"))
      (node (ref "U1") (pin "E13") (pinfunction "MDIO_E13") (pintype "bidirectional"))
      (node (ref "U1") (pin "E14") (pinfunction "MII1_RXD0_E14") (pintype "bidirectional"))
      (node (ref "U1") (pin "E15") (pinfunction "MII1_RX_ER_E15") (pintype "bidirectional"))
      (node (ref "U1") (pin "E16") (pinfunction "MII1_RX_CLK_E16") (pintype "bidirectional"))
      (node (ref "U1") (pin "E5") (pinfunction "DGND_E5") (pintype "bidirectional"))
      (node (ref "U1") (pin "E6") (pinfunction "DGND_E6") (pintype "bidirectional"))
      (node (ref "U1") (pin "E7") (pinfunction "DGND_E7") (pintype "bidirectional"))
      (node (ref "U1") (pin "E8") (pinfunction "DGND_E8") (pintype "bidirectional"))
      (node (ref "U1") (pin "E9") (pinfunction "DGND_E9") (pintype "bidirectional"))
      (node (ref "U1") (pin "F1") (pinfunction "LCD_PCLK_F1") (pintype "bidirectional"))
      (node (ref "U1") (pin "F12") (pinfunction "DGND_F12") (pintype "bidirectional"))
      (node (ref "U1") (pin "F14") (pinfunction "MII1_CRS_F14") (pintype "bidirectional"))
      (node (ref "U1") (pin "F15") (pinfunction "MII1_COL_F15") (pintype "bidirectional"))
      (node (ref "U1") (pin "F16") (pinfunction "MII1_RX_DV_F16") (pintype "bidirectional"))
      (node (ref "U1") (pin "F2") (pinfunction "LCD_HSYNC_F2") (pintype "bidirectional"))
      (node (ref "U1") (pin "F3") (pinfunction "LCD_VSYNC_F3") (pintype "bidirectional"))
      (node (ref "U1") (pin "F5") (pinfunction "DGND_F5") (pintype "bidirectional"))
      (node (ref "U1") (pin "G1") (pinfunction "LCD_DATA2_G1") (pintype "bidirectional"))
      (node (ref "U1") (pin "G12") (pinfunction "DGND_G12") (pintype "bidirectional"))
      (node (ref "U1") (pin "G14") (pinfunction "MII1_TX_EN_G14") (pintype "bidirectional"))
      (node (ref "U1") (pin "G15") (pinfunction "MII1_TXD3_G15") (pintype "bidirectional"))
      (node (ref "U1") (pin "G16") (pinfunction "MII1_TXD2_G16") (pintype "bidirectional"))
      (node (ref "U1") (pin "G2") (pinfunction "LCD_DATA1_G2") (pintype "bidirectional"))
      (node (ref "U1") (pin "G3") (pinfunction "LCD_DATA0_G3") (pintype "bidirectional"))
      (node (ref "U1") (pin "G5") (pinfunction "DGND_G5") (pintype "bidirectional"))
      (node (ref "U1") (pin "H1") (pinfunction "LCD_DATA5_H1") (pintype "bidirectional"))
      (node (ref "U1") (pin "H12") (pinfunction "DGND_H12") (pintype "bidirectional"))
      (node (ref "U1") (pin "H13") (pinfunction "DGND_H13") (pintype "bidirectional"))
      (node (ref "U1") (pin "H14") (pinfunction "MII1_TXD1_H14") (pintype "bidirectional"))
      (node (ref "U1") (pin "H15") (pinfunction "MII1_TXD0_H15") (pintype "bidirectional"))
      (node (ref "U1") (pin "H16") (pinfunction "MII1_TX_CLK_H16") (pintype "bidirectional"))
      (node (ref "U1") (pin "H2") (pinfunction "LCD_DATA4_H2") (pintype "bidirectional"))
      (node (ref "U1") (pin "H3") (pinfunction "LCD_DATA3_H3") (pintype "bidirectional"))
      (node (ref "U1") (pin "H4") (pinfunction "DGND_H4") (pintype "bidirectional"))
      (node (ref "U1") (pin "H5") (pinfunction "DGND_H5") (pintype "bidirectional"))
      (node (ref "U1") (pin "J1") (pinfunction "LCD_DATA8_J1") (pintype "bidirectional"))
      (node (ref "U1") (pin "J12") (pinfunction "DGND_J12") (pintype "bidirectional"))
      (node (ref "U1") (pin "J13") (pinfunction "DGND_J13") (pintype "bidirectional"))
      (node (ref "U1") (pin "J14") (pinfunction "RMII1_REF_CLK_J14") (pintype "bidirectional"))
      (node (ref "U1") (pin "J2") (pinfunction "LCD_DATA7_J2") (pintype "bidirectional"))
      (node (ref "U1") (pin "J3") (pinfunction "LCD_DATA6_J3") (pintype "bidirectional"))
      (node (ref "U1") (pin "J4") (pinfunction "DGND_J4") (pintype "bidirectional"))
      (node (ref "U1") (pin "J5") (pinfunction "DGND_J5") (pintype "bidirectional"))
      (node (ref "U1") (pin "K1") (pinfunction "LCD_DATA11_K1") (pintype "bidirectional"))
      (node (ref "U1") (pin "K12") (pinfunction "DGND_K12") (pintype "bidirectional"))
      (node (ref "U1") (pin "K2") (pinfunction "LCD_DATA10_K2") (pintype "bidirectional"))
      (node (ref "U1") (pin "K3") (pinfunction "LCD_DATA9_K3") (pintype "bidirectional"))
      (node (ref "U1") (pin "K5") (pinfunction "DGND_K5") (pintype "bidirectional"))
      (node (ref "U1") (pin "L1") (pinfunction "LCD_DATA14_L1") (pintype "bidirectional"))
      (node (ref "U1") (pin "L12") (pinfunction "DGND_L12") (pintype "bidirectional"))
      (node (ref "U1") (pin "L2") (pinfunction "LCD_DATA13_L2") (pintype "bidirectional"))
      (node (ref "U1") (pin "L3") (pinfunction "LCD_DATA12_L3") (pintype "bidirectional"))
      (node (ref "U1") (pin "L5") (pinfunction "DGND_L5") (pintype "bidirectional"))
      (node (ref "U1") (pin "M10") (pinfunction "DGND_M10") (pintype "bidirectional"))
      (node (ref "U1") (pin "M11") (pinfunction "DGND_M11") (pintype "bidirectional"))
      (node (ref "U1") (pin "M12") (pinfunction "DGND_M12") (pintype "bidirectional"))
      (node (ref "U1") (pin "M3") (pinfunction "LCD_DATA15_M3") (pintype "bidirectional"))
      (node (ref "U1") (pin "M5") (pinfunction "DGND_M5") (pintype "bidirectional"))
      (node (ref "U1") (pin "M6") (pinfunction "DGND_M6") (pintype "bidirectional"))
      (node (ref "U1") (pin "M7") (pinfunction "DGND_M7") (pintype "bidirectional"))
      (node (ref "U1") (pin "M8") (pinfunction "DGND_M8") (pintype "bidirectional"))
      (node (ref "U1") (pin "M9") (pinfunction "DGND_M9") (pintype "bidirectional"))
      (node (ref "U1") (pin "N8") (pinfunction "DGND_N8") (pintype "bidirectional"))
      (node (ref "U1") (pin "N9") (pinfunction "DGND_N9") (pintype "bidirectional"))
      (node (ref "U2") (pin "2") (pinfunction "GND_2") (pintype "power_in"))
      (node (ref "U3") (pin "6") (pinfunction "GND_6") (pintype "power_in"))
      (node (ref "U3") (pin "EPAD") (pinfunction "GND_EPAD") (pintype "power_in"))
      (node (ref "U4") (pin "7") (pinfunction "GND_7") (pintype "power_in"))
      (node (ref "U4") (pin "EPAD") (pinfunction "GND_EPAD") (pintype "power_in"))
      (node (ref "U5") (pin "1") (pinfunction "GND_1") (pintype "power_in"))
      (node (ref "U5") (pin "11") (pinfunction "GND_11") (pintype "power_in"))
      (node (ref "U5") (pin "12") (pinfunction "GND_12") (pintype "power_in"))
      (node (ref "U5") (pin "16") (pinfunction "GND_16") (pintype "power_in"))
      (node (ref "U5") (pin "6") (pinfunction "LBO_6") (pintype "open_collector"))
      (node (ref "U5") (pin "7") (pinfunction "LBI_7") (pintype "input"))
      (node (ref "U5") (pin "9") (pinfunction "GND_9") (pintype "power_in"))
      (node (ref "U5") (pin "PAD") (pinfunction "GND_PAD") (pintype "power_in"))
      (node (ref "U7") (pin "1") (pinfunction "GND_1") (pintype "input"))
      (node (ref "X1") (pin "2") (pinfunction "SHIELD_2") (pintype "power_in"))
      (node (ref "X1") (pin "4") (pinfunction "SHIELD_4") (pintype "power_in"))
    )
    (net (code "27") (name "MAX4211-3V3") (class "Default")
      (node (ref "C5") (pin "1") (pinfunction "1_1") (pintype "passive"))
      (node (ref "U4") (pin "1") (pinfunction "VCC_1") (pintype "power_in"))
      (node (ref "U7") (pin "2") (pinfunction "OUT_2") (pintype "passive"))
    )
    (net (code "28") (name "NRESET") (class "Default")
      (node (ref "J7") (pin "10") (pinfunction "~{RESET}_10") (pintype "passive"))
    )
    (net (code "29") (name "Net-(C2-Pad1)") (class "Default")
      (node (ref "C2") (pin "1") (pinfunction "1_1") (pintype "passive"))
      (node (ref "R36") (pin "2") (pinfunction "2_2") (pintype "passive"))
      (node (ref "R37") (pin "2") (pinfunction "2_2") (pintype "passive"))
    )
    (net (code "30") (name "Net-(C16-Pad1)") (class "Default")
      (node (ref "C16") (pin "1") (pinfunction "1_1") (pintype "passive"))
      (node (ref "X1") (pin "1") (pinfunction "1_1") (pintype "passive"))
    )
    (net (code "31") (name "Net-(CM1-CENTER)") (class "Default")
      (node (ref "CM1") (pin "RF") (pinfunction "CENTER_RF") (pintype "passive"))
      (node (ref "J2") (pin "FEED") (pinfunction "SIGNAL_FEED") (pintype "bidirectional"))
    )
    (net (code "32") (name "Net-(CM2-CENTER)") (class "Default")
      (node (ref "CM2") (pin "RF") (pinfunction "CENTER_RF") (pintype "passive"))
      (node (ref "J3") (pin "FEED") (pinfunction "SIGNAL_FEED") (pintype "bidirectional"))
    )
    (net (code "33") (name "Net-(CM3-CENTER)") (class "Default")
      (node (ref "CM3") (pin "RF") (pinfunction "CENTER_RF") (pintype "passive"))
      (node (ref "J4") (pin "FEED") (pinfunction "SIGNAL_FEED") (pintype "bidirectional"))
    )
    (net (code "34") (name "Net-(D1-PadA)") (class "Default")
      (node (ref "D1") (pin "A") (pinfunction "A_A") (pintype "passive"))
      (node (ref "R1") (pin "1") (pinfunction "1_1") (pintype "passive"))
    )
    (net (code "35") (name "Net-(D2-PadA)") (class "Default")
      (node (ref "D2") (pin "A") (pinfunction "A_A") (pintype "passive"))
      (node (ref "R2") (pin "1") (pinfunction "1_1") (pintype "passive"))
    )
    (net (code "36") (name "Net-(D3-PadA)") (class "Default")
      (node (ref "D3") (pin "A") (pinfunction "A_A") (pintype "passive"))
      (node (ref "R3") (pin "1") (pinfunction "1_1") (pintype "passive"))
    )
    (net (code "37") (name "Net-(D4-PadA)") (class "Default")
      (node (ref "D4") (pin "A") (pinfunction "A_A") (pintype "passive"))
      (node (ref "R12") (pin "1") (pinfunction "1_1") (pintype "passive"))
    )
    (net (code "38") (name "Net-(J5-VCC)") (class "Default")
      (node (ref "J5") (pin "P$4") (pinfunction "VCC_P$4") (pintype "passive"))
      (node (ref "JP8") (pin "2") (pinfunction "2_2") (pintype "passive"))
    )
    (net (code "39") (name "Net-(L2-Pad1)") (class "Default")
      (node (ref "L2") (pin "1") (pinfunction "1_1") (pintype "passive"))
      (node (ref "U5") (pin "14") (pinfunction "SW_14") (pintype "output"))
      (node (ref "U5") (pin "15") (pinfunction "SW_15") (pintype "output"))
    )
    (net (code "40") (name "Net-(Q1A-G)") (class "Default")
      (node (ref "C6") (pin "2") (pinfunction "2_2") (pintype "passive"))
      (node (ref "Q1") (pin "1") (pinfunction "G_1") (pintype "passive"))
      (node (ref "Q1") (pin "4") (pinfunction "D_4") (pintype "passive"))
      (node (ref "R15") (pin "2") (pinfunction "2_2") (pintype "passive"))
    )
    (net (code "41") (name "Net-(Q1A-S)") (class "Default")
      (node (ref "C6") (pin "1") (pinfunction "1_1") (pintype "passive"))
      (node (ref "Q1") (pin "5") (pinfunction "S_5") (pintype "passive"))
      (node (ref "R25") (pin "2") (pinfunction "2_2") (pintype "passive"))
    )
    (net (code "42") (name "Net-(Q1B-G)") (class "Default")
      (node (ref "C8") (pin "2") (pinfunction "2_2") (pintype "passive"))
      (node (ref "Q1") (pin "3") (pinfunction "G_3") (pintype "passive"))
      (node (ref "R16") (pin "2") (pinfunction "2_2") (pintype "passive"))
      (node (ref "R18") (pin "1") (pinfunction "1_1") (pintype "passive"))
    )
    (net (code "43") (name "Net-(Q3-S)") (class "Default")
      (node (ref "C4") (pin "1") (pinfunction "1_1") (pintype "passive"))
      (node (ref "Q3") (pin "4") (pinfunction "S_4") (pintype "passive"))
      (node (ref "R29") (pin "2") (pinfunction "2_2") (pintype "passive"))
      (node (ref "R35") (pin "2") (pinfunction "2_2") (pintype "passive"))
      (node (ref "U4") (pin "15") (pinfunction "RS-_15") (pintype "passive"))
      (node (ref "U7") (pin "3") (pinfunction "IN_3") (pintype "input"))
    )
    (net (code "44") (name "Net-(Q4-G)") (class "Default")
      (node (ref "Q4") (pin "3") (pinfunction "G_3") (pintype "passive"))
      (node (ref "Q5") (pin "3") (pinfunction "D_3") (pintype "passive"))
      (node (ref "R27") (pin "1") (pinfunction "1_1") (pintype "passive"))
    )
    (net (code "45") (name "Net-(R17-Pad2)") (class "Default")
      (node (ref "R17") (pin "2") (pinfunction "2_2") (pintype "passive"))
      (node (ref "TP15") (pin "1") (pinfunction "1_1") (pintype "passive"))
    )
    (net (code "46") (name "Net-(U1A-EXTINTN)") (class "Default")
      (node (ref "U1") (pin "D4") (pinfunction "EXTINTN_D4") (pintype "bidirectional"))
      (node (ref "U1") (pin "E4") (pinfunction "PMIC_NINT_E4") (pintype "output"))
    )
    (net (code "47") (name "Net-(U1A-EXT_WAKEUP)") (class "Default")
      (node (ref "U1") (pin "L4") (pinfunction "PMIC_NWAKEUP_L4") (pintype "output"))
      (node (ref "U1") (pin "M4") (pinfunction "EXT_WAKEUP_M4") (pintype "bidirectional"))
    )
    (net (code "48") (name "Net-(U1A-I2C0_SCL)") (class "Default")
      (node (ref "U1") (pin "C10") (pinfunction "I2C0_SCL_C10") (pintype "bidirectional"))
      (node (ref "U1") (pin "D10") (pinfunction "PMIC_SCL_D10") (pintype "bidirectional"))
    )
    (net (code "49") (name "Net-(U1A-I2C0_SDA)") (class "Default")
      (node (ref "U1") (pin "C11") (pinfunction "I2C0_SDA_C11") (pintype "bidirectional"))
      (node (ref "U1") (pin "D11") (pinfunction "PMIC_SDA_D11") (pintype "bidirectional"))
    )
    (net (code "50") (name "Net-(U1A-PMIC_BAT_SENSE)") (class "Default")
      (node (ref "U1") (pin "N6") (pinfunction "PMIC_TS_N6") (pintype "bidirectional"))
      (node (ref "U1") (pin "N7") (pinfunction "PMIC_BAT_SENSE_N7") (pintype "bidirectional"))
    )
    (net (code "51") (name "Net-(U1A-PMIC_LDO_PGOOD)") (class "Default")
      (node (ref "U1") (pin "N4") (pinfunction "PMIC_LDO_PGOOD_N4") (pintype "output"))
      (node (ref "U1") (pin "N5") (pinfunction "RTC_PWRONRSTN_N5") (pintype "bidirectional"))
    )
    (net (code "52") (name "Net-(U1A-PMIC_POWER_EN)") (class "Default")
      (node (ref "U1") (pin "N10") (pinfunction "PMIC_POWER_EN_N10") (pintype "output"))
      (node (ref "U1") (pin "N11") (pinfunction "PMIC_PWR_EN_N11") (pintype "input"))
    )
    (net (code "53") (name "Net-(U1A-RTC_KALDO_ENN)") (class "Default")
      (node (ref "R39") (pin "2") (pinfunction "2_2") (pintype "passive"))
      (node (ref "U1") (pin "M16") (pinfunction "RTC_KALDO_ENN_M16") (pintype "bidirectional"))
    )
    (net (code "54") (name "Net-(U1A-SYS_RTC_1P8V-PadK11)") (class "Default")
      (node (ref "U1") (pin "K11") (pinfunction "SYS_RTC_1P8V_K11") (pintype "power_in"))
      (node (ref "U1") (pin "L11") (pinfunction "SYS_RTC_1P8V_L11") (pintype "power_in"))
    )
    (net (code "55") (name "Net-(U1A-SYS_VDD1_3P3V-PadF6)") (class "Default")
      (node (ref "U1") (pin "F6") (pinfunction "SYS_VDD1_3P3V_F6") (pintype "power_in"))
      (node (ref "U1") (pin "F7") (pinfunction "SYS_VDD1_3P3V_F7") (pintype "power_in"))
      (node (ref "U1") (pin "G6") (pinfunction "SYS_VDD1_3P3V_G6") (pintype "power_in"))
      (node (ref "U1") (pin "G7") (pinfunction "SYS_VDD1_3P3V_G7") (pintype "power_in"))
    )
    (net (code "56") (name "Net-(U1A-SYS_VDD2_3P3V-PadF11)") (class "Default")
      (node (ref "U1") (pin "F11") (pinfunction "SYS_VDD2_3P3V_F11") (pintype "power_in"))
      (node (ref "U1") (pin "G11") (pinfunction "SYS_VDD2_3P3V_G11") (pintype "power_in"))
    )
    (net (code "57") (name "Net-(U1A-VIN_AC-PadP10)") (class "Default")
      (node (ref "U1") (pin "P10") (pinfunction "VIN_AC_P10") (pintype "power_in"))
      (node (ref "U1") (pin "R10") (pinfunction "VIN_AC_R10") (pintype "power_in"))
      (node (ref "U1") (pin "T10") (pinfunction "VIN_AC_T10") (pintype "power_in"))
    )
    (net (code "58") (name "Net-(U1A-VIN_BAT-PadP8)") (class "Default")
      (node (ref "U1") (pin "P8") (pinfunction "VIN_BAT_P8") (pintype "power_in"))
      (node (ref "U1") (pin "R8") (pinfunction "VIN_BAT_R8") (pintype "power_in"))
      (node (ref "U1") (pin "T8") (pinfunction "VIN_BAT_T8") (pintype "power_in"))
    )
    (net (code "59") (name "Net-(U1A-VIN_USB-PadP9)") (class "Default")
      (node (ref "U1") (pin "P9") (pinfunction "VIN_USB_P9") (pintype "power_in"))
      (node (ref "U1") (pin "R9") (pinfunction "VIN_USB_R9") (pintype "power_in"))
      (node (ref "U1") (pin "T9") (pinfunction "VIN_USB_T9") (pintype "power_in"))
    )
    (net (code "60") (name "Net-(U1F-VDDS_DDR)") (class "Default")
      (node (ref "TP_DDR") (pin "1") (pinfunction "1_1") (pintype "passive"))
      (node (ref "U1") (pin "F4") (pinfunction "VDDS_DDR_F4") (pintype "bidirectional"))
    )
    (net (code "61") (name "Net-(U1F-VDDS_PLL)") (class "Default")
      (node (ref "TP_PLL") (pin "1") (pinfunction "1_1") (pintype "passive"))
      (node (ref "U1") (pin "G13") (pinfunction "VDDS_PLL_G13") (pintype "bidirectional"))
    )
    (net (code "62") (name "Net-(U1F-VDD_CORE)") (class "Default")
      (node (ref "TP_CORE") (pin "1") (pinfunction "1_1") (pintype "passive"))
      (node (ref "U1") (pin "G4") (pinfunction "VDD_CORE_G4") (pintype "bidirectional"))
    )
    (net (code "63") (name "Net-(U1F-VDD_MPU)") (class "Default")
      (node (ref "TP_MPU") (pin "1") (pinfunction "1_1") (pintype "passive"))
      (node (ref "U1") (pin "F13") (pinfunction "VDD_MPU_F13") (pintype "bidirectional"))
    )
    (net (code "64") (name "Net-(U3-IO3)") (class "Default")
      (node (ref "TP2") (pin "1") (pinfunction "1_1") (pintype "passive"))
      (node (ref "U3") (pin "8") (pinfunction "IO3_8") (pintype "bidirectional"))
    )
    (net (code "65") (name "Net-(U3-IO4)") (class "Default")
      (node (ref "TP3") (pin "1") (pinfunction "1_1") (pintype "passive"))
      (node (ref "U3") (pin "9") (pinfunction "IO4_9") (pintype "bidirectional"))
    )
    (net (code "66") (name "Net-(U3-IO5)") (class "Default")
      (node (ref "TP4") (pin "1") (pinfunction "1_1") (pintype "passive"))
      (node (ref "U3") (pin "10") (pinfunction "IO5_10") (pintype "bidirectional"))
    )
    (net (code "67") (name "Net-(U3-IO6)") (class "Default")
      (node (ref "TP5") (pin "1") (pinfunction "1_1") (pintype "passive"))
      (node (ref "U3") (pin "11") (pinfunction "IO6_11") (pintype "bidirectional"))
    )
    (net (code "68") (name "Net-(U3-IO7)") (class "Default")
      (node (ref "R12") (pin "2") (pinfunction "2_2") (pintype "passive"))
      (node (ref "TP10") (pin "1") (pinfunction "1_1") (pintype "passive"))
      (node (ref "U3") (pin "12") (pinfunction "IO7_12") (pintype "bidirectional"))
    )
    (net (code "69") (name "Net-(U3-~{RESET})") (class "Default")
      (node (ref "R26") (pin "1") (pinfunction "1_1") (pintype "passive"))
      (node (ref "U3") (pin "13") (pinfunction "~{RESET}_13") (pintype "input"))
    )
    (net (code "70") (name "Net-(U4-CIN1+)") (class "Default")
      (node (ref "R33") (pin "1") (pinfunction "1_1") (pintype "passive"))
      (node (ref "R34") (pin "2") (pinfunction "2_2") (pintype "passive"))
      (node (ref "TP11") (pin "1") (pinfunction "1_1") (pintype "passive"))
      (node (ref "U4") (pin "10") (pinfunction "CIN1+_10") (pintype "input"))
    )
    (net (code "71") (name "Net-(U4-CIN1-)") (class "Default")
      (node (ref "R31") (pin "1") (pinfunction "1_1") (pintype "passive"))
      (node (ref "R32") (pin "2") (pinfunction "2_2") (pintype "passive"))
      (node (ref "TP12") (pin "1") (pinfunction "1_1") (pintype "passive"))
      (node (ref "U4") (pin "11") (pinfunction "CIN1-_11") (pintype "input"))
    )
    (net (code "72") (name "Net-(U4-CIN2+)") (class "Default")
      (node (ref "R33") (pin "2") (pinfunction "2_2") (pintype "passive"))
      (node (ref "U4") (pin "12") (pinfunction "REF_12") (pintype "output"))
      (node (ref "U4") (pin "8") (pinfunction "CIN2+_8") (pintype "input"))
    )
    (net (code "73") (name "Net-(U4-INHIBIT)") (class "Default")
      (node (ref "R37") (pin "1") (pinfunction "1_1") (pintype "passive"))
      (node (ref "U4") (pin "5") (pinfunction "INHIBIT_5") (pintype "input"))
    )
    (net (code "74") (name "Net-(U4-IOUT)") (class "Default")
      (node (ref "R31") (pin "2") (pinfunction "2_2") (pintype "passive"))
      (node (ref "U4") (pin "14") (pinfunction "IOUT_14") (pintype "output"))
    )
    (net (code "75") (name "Net-(U4-POUT)") (class "Default")
      (node (ref "TP6") (pin "1") (pinfunction "1_1") (pintype "passive"))
      (node (ref "U4") (pin "13") (pinfunction "POUT_13") (pintype "output"))
    )
    (net (code "76") (name "Net-(U4-RS+)") (class "Default")
      (node (ref "Q4") (pin "1") (pinfunction "D_1") (pintype "passive"))
      (node (ref "Q4") (pin "2") (pinfunction "D_2") (pintype "passive"))
      (node (ref "Q4") (pin "5") (pinfunction "D_5") (pintype "passive"))
      (node (ref "Q4") (pin "6") (pinfunction "D_6") (pintype "passive"))
      (node (ref "R29") (pin "1") (pinfunction "1_1") (pintype "passive"))
      (node (ref "U4") (pin "16") (pinfunction "RS+_16") (pintype "passive"))
    )
    (net (code "77") (name "Net-(U5-PG)") (class "Default")
      (node (ref "TP16") (pin "1") (pinfunction "1_1") (pintype "passive"))
      (node (ref "U5") (pin "13") (pinfunction "PG_13") (pintype "open_collector"))
    )
    (net (code "78") (name "Net-(U5-SYNC)") (class "Default")
      (node (ref "R10") (pin "2") (pinfunction "2_2") (pintype "passive"))
      (node (ref "R7") (pin "1") (pinfunction "1_1") (pintype "passive"))
      (node (ref "TP19") (pin "1") (pinfunction "1_1") (pintype "passive"))
      (node (ref "U5") (pin "5") (pinfunction "SYNC_5") (pintype "input"))
    )
    (net (code "79") (name "Net-(X1-2)") (class "Default")
      (node (ref "C11") (pin "1") (pinfunction "1_1") (pintype "passive"))
      (node (ref "X1") (pin "3") (pinfunction "2_3") (pintype "passive"))
    )
    (net (code "80") (name "ON{slash}~{OFF}") (class "Default")
      (node (ref "Q5") (pin "1") (pinfunction "G_1") (pintype "passive"))
      (node (ref "R28") (pin "2") (pinfunction "2_2") (pintype "passive"))
      (node (ref "TP13") (pin "1") (pinfunction "1_1") (pintype "passive"))
      (node (ref "U3") (pin "4") (pinfunction "IO0_4") (pintype "bidirectional"))
    )
    (net (code "81") (name "OPD_PWR") (class "Default")
      (node (ref "J6") (pin "19") (pinfunction "19_19") (pintype "passive"))
      (node (ref "J6") (pin "20") (pinfunction "20_20") (pintype "passive"))
      (node (ref "R4") (pin "1") (pinfunction "1_1") (pintype "passive"))
    )
    (net (code "82") (name "OPD_SCL") (class "Default")
      (node (ref "J6") (pin "17") (pinfunction "17_17") (pintype "passive"))
      (node (ref "J6") (pin "18") (pinfunction "18_18") (pintype "passive"))
      (node (ref "R24") (pin "1") (pinfunction "1_1") (pintype "passive"))
    )
    (net (code "83") (name "OPD_SDA") (class "Default")
      (node (ref "J6") (pin "15") (pinfunction "15_15") (pintype "passive"))
      (node (ref "J6") (pin "16") (pinfunction "16_16") (pintype "passive"))
      (node (ref "R25") (pin "1") (pinfunction "1_1") (pintype "passive"))
    )
    (net (code "84") (name "PA0") (class "Default")
      (node (ref "JP4") (pin "2") (pinfunction "2_2") (pintype "passive"))
      (node (ref "R3") (pin "2") (pinfunction "2_2") (pintype "passive"))
    )
    (net (code "85") (name "PA1") (class "Default")
      (node (ref "JP4") (pin "4") (pinfunction "4_4") (pintype "passive"))
    )
    (net (code "86") (name "PA2{slash}USART2_TX") (class "Default")
      (node (ref "J5") (pin "P$2") (pinfunction "TXO_P$2") (pintype "passive"))
      (node (ref "JP4") (pin "6") (pinfunction "6_6") (pintype "passive"))
    )
    (net (code "87") (name "PA3{slash}USART2_RX") (class "Default")
      (node (ref "J5") (pin "P$3") (pinfunction "RXI_P$3") (pintype "passive"))
      (node (ref "JP4") (pin "8") (pinfunction "8_8") (pintype "passive"))
    )
    (net (code "88") (name "PA4") (class "Default")
      (node (ref "JP4") (pin "10") (pinfunction "10_10") (pintype "passive"))
    )
    (net (code "89") (name "PA5{slash}SPI1_SCK") (class "Default")
      (node (ref "JP4") (pin "12") (pinfunction "12_12") (pintype "passive"))
    )
    (net (code "90") (name "PA6{slash}SPI1_MISO") (class "Default")
      (node (ref "JP4") (pin "14") (pinfunction "14_14") (pintype "passive"))
    )
    (net (code "91") (name "PA7{slash}SPI1_MOSI") (class "Default")
      (node (ref "JP4") (pin "16") (pinfunction "16_16") (pintype "passive"))
    )
    (net (code "92") (name "PA8") (class "Default")
      (node (ref "JP4") (pin "13") (pinfunction "13_13") (pintype "passive"))
    )
    (net (code "93") (name "PA15") (class "Default")
      (node (ref "JP4") (pin "11") (pinfunction "11_11") (pintype "passive"))
    )
    (net (code "94") (name "PB0") (class "Default")
      (node (ref "JP4") (pin "18") (pinfunction "18_18") (pintype "passive"))
    )
    (net (code "95") (name "PB1") (class "Default")
      (node (ref "JP4") (pin "20") (pinfunction "20_20") (pintype "passive"))
    )
    (net (code "96") (name "PB3") (class "Default")
      (node (ref "JP4") (pin "9") (pinfunction "9_9") (pintype "passive"))
    )
    (net (code "97") (name "PB4") (class "Default")
      (node (ref "JP4") (pin "7") (pinfunction "7_7") (pintype "passive"))
    )
    (net (code "98") (name "PB5") (class "Default")
      (node (ref "JP4") (pin "5") (pinfunction "5_5") (pintype "passive"))
    )
    (net (code "99") (name "PB6{slash}SCL") (class "Default")
      (node (ref "JP4") (pin "3") (pinfunction "3_3") (pintype "passive"))
    )
    (net (code "100") (name "PB7{slash}SDA") (class "Default")
      (node (ref "JP4") (pin "1") (pinfunction "1_1") (pintype "passive"))
    )
    (net (code "101") (name "PEN-SCL-FILT") (class "Default")
      (node (ref "R13") (pin "1") (pinfunction "1_1") (pintype "passive"))
      (node (ref "R21") (pin "1") (pinfunction "1_1") (pintype "passive"))
      (node (ref "R24") (pin "2") (pinfunction "2_2") (pintype "passive"))
      (node (ref "R6") (pin "1") (pinfunction "1_1") (pintype "passive"))
      (node (ref "TP18") (pin "1") (pinfunction "1_1") (pintype "passive"))
      (node (ref "U3") (pin "15") (pinfunction "SCL_15") (pintype "input"))
    )
    (net (code "102") (name "PEN-SDA-FILT") (class "Default")
      (node (ref "Q1") (pin "6") (pinfunction "D_6") (pintype "passive"))
      (node (ref "R16") (pin "1") (pinfunction "1_1") (pintype "passive"))
      (node (ref "R19") (pin "2") (pinfunction "2_2") (pintype "passive"))
      (node (ref "R23") (pin "2") (pinfunction "2_2") (pintype "passive"))
      (node (ref "R9") (pin "2") (pinfunction "2_2") (pintype "passive"))
      (node (ref "TP20") (pin "1") (pinfunction "1_1") (pintype "passive"))
      (node (ref "U3") (pin "16") (pinfunction "SDA_16") (pintype "bidirectional"))
    )
    (net (code "103") (name "SPARE1") (class "Default")
      (node (ref "J6") (pin "13") (pinfunction "13_13") (pintype "passive"))
      (node (ref "J6") (pin "14") (pinfunction "14_14") (pintype "passive"))
      (node (ref "JP11") (pin "8") (pinfunction "8_8") (pintype "passive"))
    )
    (net (code "104") (name "SPARE2") (class "Default")
      (node (ref "J6") (pin "11") (pinfunction "11_11") (pintype "passive"))
      (node (ref "J6") (pin "12") (pinfunction "12_12") (pintype "passive"))
      (node (ref "JP11") (pin "7") (pinfunction "7_7") (pintype "passive"))
    )
    (net (code "105") (name "SPARE3") (class "Default")
      (node (ref "J6") (pin "10") (pinfunction "10_10") (pintype "passive"))
      (node (ref "J6") (pin "9") (pinfunction "9_9") (pintype "passive"))
      (node (ref "JP11") (pin "6") (pinfunction "6_6") (pintype "passive"))
    )
    (net (code "106") (name "SPARE4") (class "Default")
      (node (ref "J6") (pin "7") (pinfunction "7_7") (pintype "passive"))
      (node (ref "J6") (pin "8") (pinfunction "8_8") (pintype "passive"))
      (node (ref "JP11") (pin "5") (pinfunction "5_5") (pintype "passive"))
    )
    (net (code "107") (name "SPARE5") (class "Default")
      (node (ref "J6") (pin "5") (pinfunction "5_5") (pintype "passive"))
      (node (ref "J6") (pin "6") (pinfunction "6_6") (pintype "passive"))
      (node (ref "JP11") (pin "4") (pinfunction "4_4") (pintype "passive"))
    )
    (net (code "108") (name "SPARE6") (class "Default")
      (node (ref "J6") (pin "3") (pinfunction "3_3") (pintype "passive"))
      (node (ref "J6") (pin "4") (pinfunction "4_4") (pintype "passive"))
      (node (ref "JP11") (pin "3") (pinfunction "3_3") (pintype "passive"))
    )
    (net (code "109") (name "SPARE7") (class "Default")
      (node (ref "J6") (pin "1") (pinfunction "1_1") (pintype "passive"))
      (node (ref "J6") (pin "2") (pinfunction "2_2") (pintype "passive"))
      (node (ref "JP11") (pin "2") (pinfunction "2_2") (pintype "passive"))
    )
    (net (code "110") (name "VBUS") (class "Default")
      (node (ref "J6") (pin "25") (pinfunction "25_25") (pintype "passive"))
      (node (ref "J6") (pin "26") (pinfunction "26_26") (pintype "passive"))
      (node (ref "J6") (pin "27") (pinfunction "27_27") (pintype "passive"))
      (node (ref "J6") (pin "28") (pinfunction "28_28") (pintype "passive"))
      (node (ref "JP10") (pin "1") (pinfunction "1_1") (pintype "passive"))
      (node (ref "JP10") (pin "2") (pinfunction "2_2") (pintype "passive"))
      (node (ref "JP10") (pin "3") (pinfunction "3_3") (pintype "passive"))
      (node (ref "JP10") (pin "4") (pinfunction "4_4") (pintype "passive"))
      (node (ref "Q4") (pin "4") (pinfunction "S_4") (pintype "passive"))
      (node (ref "R27") (pin "2") (pinfunction "2_2") (pintype "passive"))
    )
    (net (code "111") (name "VBUSP") (class "Default")
      (node (ref "C10") (pin "1") (pinfunction "1_1") (pintype "passive"))
      (node (ref "C2") (pin "2") (pinfunction "2_2") (pintype "passive"))
      (node (ref "C7") (pin "1") (pinfunction "1_1") (pintype "passive"))
      (node (ref "JP1") (pin "5") (pinfunction "5_5") (pintype "passive"))
      (node (ref "JP3") (pin "1") (pinfunction "1_1") (pintype "passive"))
      (node (ref "JP3") (pin "2") (pinfunction "2_2") (pintype "passive"))
      (node (ref "JP3") (pin "3") (pinfunction "3_3") (pintype "passive"))
      (node (ref "JP8") (pin "1") (pinfunction "1_1") (pintype "passive"))
      (node (ref "Q3") (pin "1") (pinfunction "D_1") (pintype "passive"))
      (node (ref "Q3") (pin "2") (pinfunction "D_2") (pintype "passive"))
      (node (ref "Q3") (pin "5") (pinfunction "D_5") (pintype "passive"))
      (node (ref "Q3") (pin "6") (pinfunction "D_6") (pintype "passive"))
      (node (ref "R1") (pin "2") (pinfunction "2_2") (pintype "passive"))
      (node (ref "R7") (pin "2") (pinfunction "2_2") (pintype "passive"))
      (node (ref "TP9") (pin "1") (pinfunction "1_1") (pintype "passive"))
      (node (ref "U5") (pin "2") (pinfunction "VIN_2") (pintype "power_in"))
      (node (ref "U5") (pin "3") (pinfunction "VIN_3") (pintype "power_in"))
      (node (ref "U5") (pin "4") (pinfunction "EN_4") (pintype "input"))
      (node (ref "U5") (pin "8") (pinfunction "VIN_8") (pintype "power_in"))
    )
    (net (code "112") (name "VPD") (class "Default")
      (node (ref "C1") (pin "2") (pinfunction "2_2") (pintype "passive"))
      (node (ref "C8") (pin "1") (pinfunction "1_1") (pintype "passive"))
      (node (ref "Q1") (pin "2") (pinfunction "S_2") (pintype "passive"))
      (node (ref "R11") (pin "2") (pinfunction "2_2") (pintype "passive"))
      (node (ref "R18") (pin "2") (pinfunction "2_2") (pintype "passive"))
      (node (ref "R20") (pin "2") (pinfunction "2_2") (pintype "passive"))
      (node (ref "R26") (pin "2") (pinfunction "2_2") (pintype "passive"))
      (node (ref "R38") (pin "2") (pinfunction "2_2") (pintype "passive"))
      (node (ref "R4") (pin "2") (pinfunction "2_2") (pintype "passive"))
      (node (ref "R5") (pin "2") (pinfunction "2_2") (pintype "passive"))
      (node (ref "TP1") (pin "1") (pinfunction "1_1") (pintype "passive"))
      (node (ref "U3") (pin "14") (pinfunction "V+_14") (pintype "power_in"))
    )
    (net (code "113") (name "Vout") (class "Default")
      (node (ref "U1") (pin "K6") (pinfunction "SYS_VOUT_K6") (pintype "power_in"))
      (node (ref "U1") (pin "K7") (pinfunction "SYS_VOUT_K7") (pintype "power_in"))
      (node (ref "U1") (pin "L6") (pinfunction "SYS_VOUT_L6") (pintype "power_in"))
      (node (ref "U1") (pin "L7") (pinfunction "SYS_VOUT_L7") (pintype "power_in"))
    )
    (net (code "114") (name "unconnected-(J5-CTS-PadP$5)") (class "Default")
      (node (ref "J5") (pin "P$5") (pinfunction "CTS_P$5") (pintype "passive"))
    )
    (net (code "115") (name "unconnected-(J5-DTR-PadP$1)") (class "Default")
      (node (ref "J5") (pin "P$1") (pinfunction "DTR_P$1") (pintype "passive"))
    )
    (net (code "116") (name "unconnected-(J7-NC{slash}TDI-Pad8)") (class "Default")
      (node (ref "J7") (pin "8") (pinfunction "NC/TDI_8") (pintype "passive"))
    )
    (net (code "117") (name "unconnected-(J7-SWDCLK{slash}TCK-Pad4)") (class "Default")
      (node (ref "J7") (pin "4") (pinfunction "SWDCLK/TCK_4") (pintype "passive"))
    )
    (net (code "118") (name "unconnected-(J7-SWDIO{slash}TMS-Pad2)") (class "Default")
      (node (ref "J7") (pin "2") (pinfunction "SWDIO/TMS_2") (pintype "passive"))
    )
    (net (code "119") (name "unconnected-(J7-SWO{slash}TDO-Pad6)") (class "Default")
      (node (ref "J7") (pin "6") (pinfunction "SWO/TDO_6") (pintype "passive"))
    )
    (net (code "120") (name "unconnected-(JP11-Pad1)") (class "Default")
      (node (ref "JP11") (pin "1") (pinfunction "1_1") (pintype "passive"))
    )
    (net (code "121") (name "unconnected-(U1A-EEPROM_WP-PadM2)") (class "Default")
      (node (ref "U1") (pin "M2") (pinfunction "EEPROM_WP_M2") (pintype "bidirectional"))
    )
    (net (code "122") (name "unconnected-(U1A-PMIC_NRESET-PadM13)") (class "Default")
      (node (ref "U1") (pin "M13") (pinfunction "PMIC_NRESET_M13") (pintype "bidirectional"))
    )
    (net (code "123") (name "unconnected-(U1A-PMIC_PB_IN-PadT11)") (class "Default")
      (node (ref "U1") (pin "T11") (pinfunction "PMIC_PB_IN_T11") (pintype "bidirectional"))
    )
    (net (code "124") (name "unconnected-(U1A-PMIC_PGOOD-PadN12)") (class "Default")
      (node (ref "U1") (pin "N12") (pinfunction "PMIC_PGOOD_N12") (pintype "output"))
    )
    (net (code "125") (name "unconnected-(U1A-PWRONRSTN-PadP11)") (class "Default")
      (node (ref "U1") (pin "P11") (pinfunction "PWRONRSTN_P11") (pintype "bidirectional"))
    )
    (net (code "126") (name "unconnected-(U1A-WARMRSTN-PadR11)") (class "Default")
      (node (ref "U1") (pin "R11") (pinfunction "WARMRSTN_R11") (pintype "bidirectional"))
    )
    (net (code "127") (name "unconnected-(U1B-AGND_ADC-PadA9)") (class "Default")
      (node (ref "U1") (pin "A9") (pinfunction "AGND_ADC_A9") (pintype "bidirectional"))
    )
    (net (code "128") (name "unconnected-(U1B-AIN0-PadA8)") (class "Default")
      (node (ref "U1") (pin "A8") (pinfunction "AIN0_A8") (pintype "bidirectional"))
    )
    (net (code "129") (name "unconnected-(U1B-AIN1-PadB8)") (class "Default")
      (node (ref "U1") (pin "B8") (pinfunction "AIN1_B8") (pintype "bidirectional"))
    )
    (net (code "130") (name "unconnected-(U1B-AIN2-PadB6)") (class "Default")
      (node (ref "U1") (pin "B6") (pinfunction "AIN2_B6") (pintype "bidirectional"))
    )
    (net (code "131") (name "unconnected-(U1B-AIN3-PadC6)") (class "Default")
      (node (ref "U1") (pin "C6") (pinfunction "AIN3_C6") (pintype "bidirectional"))
    )
    (net (code "132") (name "unconnected-(U1B-AIN4-PadC7)") (class "Default")
      (node (ref "U1") (pin "C7") (pinfunction "AIN4_C7") (pintype "bidirectional"))
    )
    (net (code "133") (name "unconnected-(U1B-AIN5-PadC8)") (class "Default")
      (node (ref "U1") (pin "C8") (pinfunction "AIN5_C8") (pintype "bidirectional"))
    )
    (net (code "134") (name "unconnected-(U1B-AIN6-PadC9)") (class "Default")
      (node (ref "U1") (pin "C9") (pinfunction "AIN6_C9") (pintype "bidirectional"))
    )
    (net (code "135") (name "unconnected-(U1B-AIN7-PadD7)") (class "Default")
      (node (ref "U1") (pin "D7") (pinfunction "AIN7_D7") (pintype "bidirectional"))
    )
    (net (code "136") (name "unconnected-(U1B-EMU0-PadE2)") (class "Default")
      (node (ref "U1") (pin "E2") (pinfunction "EMU0_E2") (pintype "bidirectional"))
    )
    (net (code "137") (name "unconnected-(U1B-EMU1-PadE3)") (class "Default")
      (node (ref "U1") (pin "E3") (pinfunction "EMU1_E3") (pintype "bidirectional"))
    )
    (net (code "138") (name "unconnected-(U1B-OSC0_GND-PadN15)") (class "Default")
      (node (ref "U1") (pin "N15") (pinfunction "OSC0_GND_N15") (pintype "bidirectional"))
    )
    (net (code "139") (name "unconnected-(U1B-OSC0_IN-PadP16)") (class "Default")
      (node (ref "U1") (pin "P16") (pinfunction "OSC0_IN_P16") (pintype "bidirectional"))
    )
    (net (code "140") (name "unconnected-(U1B-OSC0_OUT-PadN16)") (class "Default")
      (node (ref "U1") (pin "N16") (pinfunction "OSC0_OUT_N16") (pintype "bidirectional"))
    )
    (net (code "141") (name "unconnected-(U1B-OSC1_GND-PadB5)") (class "Default")
      (node (ref "U1") (pin "B5") (pinfunction "OSC1_GND_B5") (pintype "bidirectional"))
    )
    (net (code "142") (name "unconnected-(U1B-OSC1_IN-PadA6)") (class "Default")
      (node (ref "U1") (pin "A6") (pinfunction "OSC1_IN_A6") (pintype "bidirectional"))
    )
    (net (code "143") (name "unconnected-(U1B-OSC1_OUT-PadA5)") (class "Default")
      (node (ref "U1") (pin "A5") (pinfunction "OSC1_OUT_A5") (pintype "bidirectional"))
    )
    (net (code "144") (name "unconnected-(U1B-PMIC_MUX_IN-PadN13)") (class "Default")
      (node (ref "U1") (pin "N13") (pinfunction "PMIC_MUX_IN_N13") (pintype "bidirectional"))
    )
    (net (code "145") (name "unconnected-(U1B-PMIC_MUX_OUT-PadD6)") (class "Default")
      (node (ref "U1") (pin "D6") (pinfunction "PMIC_MUX_OUT_D6") (pintype "bidirectional"))
    )
    (net (code "146") (name "unconnected-(U1B-SYS_ADC_1P8V-PadA7)") (class "Default")
      (node (ref "U1") (pin "A7") (pinfunction "SYS_ADC_1P8V_A7") (pintype "bidirectional"))
    )
    (net (code "147") (name "unconnected-(U1B-TCK-PadD1)") (class "Default")
      (node (ref "U1") (pin "D1") (pinfunction "TCK_D1") (pintype "bidirectional"))
    )
    (net (code "148") (name "unconnected-(U1B-TDI-PadC1)") (class "Default")
      (node (ref "U1") (pin "C1") (pinfunction "TDI_C1") (pintype "bidirectional"))
    )
    (net (code "149") (name "unconnected-(U1B-TDO-PadC2)") (class "Default")
      (node (ref "U1") (pin "C2") (pinfunction "TDO_C2") (pintype "bidirectional"))
    )
    (net (code "150") (name "unconnected-(U1B-TMS-PadD2)") (class "Default")
      (node (ref "U1") (pin "D2") (pinfunction "TMS_D2") (pintype "bidirectional"))
    )
    (net (code "151") (name "unconnected-(U1B-TRSTN-PadD3)") (class "Default")
      (node (ref "U1") (pin "D3") (pinfunction "TRSTN_D3") (pintype "bidirectional"))
    )
    (net (code "152") (name "unconnected-(U1B-USB0_CE-PadK13)") (class "Default")
      (node (ref "U1") (pin "K13") (pinfunction "USB0_CE_K13") (pintype "bidirectional"))
    )
    (net (code "153") (name "unconnected-(U1B-USB0_DM-PadK16)") (class "Default")
      (node (ref "U1") (pin "K16") (pinfunction "USB0_DM_K16") (pintype "bidirectional"))
    )
    (net (code "154") (name "unconnected-(U1B-USB0_DP-PadK15)") (class "Default")
      (node (ref "U1") (pin "K15") (pinfunction "USB0_DP_K15") (pintype "bidirectional"))
    )
    (net (code "155") (name "unconnected-(U1B-USB0_DRVVBUS-PadJ15)") (class "Default")
      (node (ref "U1") (pin "J15") (pinfunction "USB0_DRVVBUS_J15") (pintype "bidirectional"))
    )
    (net (code "156") (name "unconnected-(U1B-USB0_ID-PadK14)") (class "Default")
      (node (ref "U1") (pin "K14") (pinfunction "USB0_ID_K14") (pintype "bidirectional"))
    )
    (net (code "157") (name "unconnected-(U1B-USB0_VBUS-PadJ16)") (class "Default")
      (node (ref "U1") (pin "J16") (pinfunction "USB0_VBUS_J16") (pintype "bidirectional"))
    )
    (net (code "158") (name "unconnected-(U1B-USB1_CE-PadL13)") (class "Default")
      (node (ref "U1") (pin "L13") (pinfunction "USB1_CE_L13") (pintype "bidirectional"))
    )
    (net (code "159") (name "unconnected-(U1B-USB1_DM-PadL16)") (class "Default")
      (node (ref "U1") (pin "L16") (pinfunction "USB1_DM_L16") (pintype "bidirectional"))
    )
    (net (code "160") (name "unconnected-(U1B-USB1_DP-PadL15)") (class "Default")
      (node (ref "U1") (pin "L15") (pinfunction "USB1_DP_L15") (pintype "bidirectional"))
    )
    (net (code "161") (name "unconnected-(U1B-USB1_DRVVBUS-PadM14)") (class "Default")
      (node (ref "U1") (pin "M14") (pinfunction "USB1_DRVVBUS_M14") (pintype "bidirectional"))
    )
    (net (code "162") (name "unconnected-(U1B-USB1_ID-PadL14)") (class "Default")
      (node (ref "U1") (pin "L14") (pinfunction "USB1_ID_L14") (pintype "bidirectional"))
    )
    (net (code "163") (name "unconnected-(U1B-USB1_VBUS-PadM15)") (class "Default")
      (node (ref "U1") (pin "M15") (pinfunction "USB1_VBUS_M15") (pintype "bidirectional"))
    )
    (net (code "164") (name "unconnected-(U1B-VREFN-PadB9)") (class "Default")
      (node (ref "U1") (pin "B9") (pinfunction "VREFN_B9") (pintype "bidirectional"))
    )
    (net (code "165") (name "unconnected-(U1B-VREFP-PadB7)") (class "Default")
      (node (ref "U1") (pin "B7") (pinfunction "VREFP_B7") (pintype "bidirectional"))
    )
    (net (code "166") (name "unconnected-(U1C-ECAP0_IN_PWM0_OUT-PadC5)") (class "Default")
      (node (ref "U1") (pin "C5") (pinfunction "ECAP0_IN_PWM0_OUT_C5") (pintype "bidirectional"))
    )
    (net (code "167") (name "unconnected-(U1C-GPMC_A0-PadT12)") (class "Default")
      (node (ref "U1") (pin "T12") (pinfunction "GPMC_A0_T12") (pintype "bidirectional"))
    )
    (net (code "168") (name "unconnected-(U1C-GPMC_A1-PadR12)") (class "Default")
      (node (ref "U1") (pin "R12") (pinfunction "GPMC_A1_R12") (pintype "bidirectional"))
    )
    (net (code "169") (name "unconnected-(U1C-GPMC_A2-PadP12)") (class "Default")
      (node (ref "U1") (pin "P12") (pinfunction "GPMC_A2_P12") (pintype "bidirectional"))
    )
    (net (code "170") (name "unconnected-(U1C-GPMC_A3-PadT13)") (class "Default")
      (node (ref "U1") (pin "T13") (pinfunction "GPMC_A3_T13") (pintype "bidirectional"))
    )
    (net (code "171") (name "unconnected-(U1C-GPMC_A4-PadR13)") (class "Default")
      (node (ref "U1") (pin "R13") (pinfunction "GPMC_A4_R13") (pintype "bidirectional"))
    )
    (net (code "172") (name "unconnected-(U1C-GPMC_A5-PadP13)") (class "Default")
      (node (ref "U1") (pin "P13") (pinfunction "GPMC_A5_P13") (pintype "bidirectional"))
    )
    (net (code "173") (name "unconnected-(U1C-GPMC_A6-PadT14)") (class "Default")
      (node (ref "U1") (pin "T14") (pinfunction "GPMC_A6_T14") (pintype "bidirectional"))
    )
    (net (code "174") (name "unconnected-(U1C-GPMC_A7-PadR14)") (class "Default")
      (node (ref "U1") (pin "R14") (pinfunction "GPMC_A7_R14") (pintype "bidirectional"))
    )
    (net (code "175") (name "unconnected-(U1C-GPMC_A8-PadP14)") (class "Default")
      (node (ref "U1") (pin "P14") (pinfunction "GPMC_A8_P14") (pintype "bidirectional"))
    )
    (net (code "176") (name "unconnected-(U1C-GPMC_A9-PadT15)") (class "Default")
      (node (ref "U1") (pin "T15") (pinfunction "GPMC_A9_T15") (pintype "bidirectional"))
    )
    (net (code "177") (name "unconnected-(U1C-GPMC_A10-PadR15)") (class "Default")
      (node (ref "U1") (pin "R15") (pinfunction "GPMC_A10_R15") (pintype "bidirectional"))
    )
    (net (code "178") (name "unconnected-(U1C-GPMC_A11-PadT16)") (class "Default")
      (node (ref "U1") (pin "T16") (pinfunction "GPMC_A11_T16") (pintype "bidirectional"))
    )
    (net (code "179") (name "unconnected-(U1C-GPMC_AD0-PadR3)") (class "Default")
      (node (ref "U1") (pin "R3") (pinfunction "GPMC_AD0_R3") (pintype "bidirectional"))
    )
    (net (code "180") (name "unconnected-(U1C-GPMC_AD1-PadR2)") (class "Default")
      (node (ref "U1") (pin "R2") (pinfunction "GPMC_AD1_R2") (pintype "bidirectional"))
    )
    (net (code "181") (name "unconnected-(U1C-GPMC_AD2-PadR1)") (class "Default")
      (node (ref "U1") (pin "R1") (pinfunction "GPMC_AD2_R1") (pintype "bidirectional"))
    )
    (net (code "182") (name "unconnected-(U1C-GPMC_AD3-PadT3)") (class "Default")
      (node (ref "U1") (pin "T3") (pinfunction "GPMC_AD3_T3") (pintype "bidirectional"))
    )
    (net (code "183") (name "unconnected-(U1C-GPMC_AD4-PadT2)") (class "Default")
      (node (ref "U1") (pin "T2") (pinfunction "GPMC_AD4_T2") (pintype "bidirectional"))
    )
    (net (code "184") (name "unconnected-(U1C-GPMC_AD5-PadT1)") (class "Default")
      (node (ref "U1") (pin "T1") (pinfunction "GPMC_AD5_T1") (pintype "bidirectional"))
    )
    (net (code "185") (name "unconnected-(U1C-GPMC_AD6-PadP4)") (class "Default")
      (node (ref "U1") (pin "P4") (pinfunction "GPMC_AD6_P4") (pintype "bidirectional"))
    )
    (net (code "186") (name "unconnected-(U1C-GPMC_AD7-PadR4)") (class "Default")
      (node (ref "U1") (pin "R4") (pinfunction "GPMC_AD7_R4") (pintype "bidirectional"))
    )
    (net (code "187") (name "unconnected-(U1C-GPMC_AD8-PadT4)") (class "Default")
      (node (ref "U1") (pin "T4") (pinfunction "GPMC_AD8_T4") (pintype "bidirectional"))
    )
    (net (code "188") (name "unconnected-(U1C-GPMC_AD9-PadP5)") (class "Default")
      (node (ref "U1") (pin "P5") (pinfunction "GPMC_AD9_P5") (pintype "bidirectional"))
    )
    (net (code "189") (name "unconnected-(U1C-GPMC_AD10-PadR5)") (class "Default")
      (node (ref "U1") (pin "R5") (pinfunction "GPMC_AD10_R5") (pintype "bidirectional"))
    )
    (net (code "190") (name "unconnected-(U1C-GPMC_AD11-PadT5)") (class "Default")
      (node (ref "U1") (pin "T5") (pinfunction "GPMC_AD11_T5") (pintype "bidirectional"))
    )
    (net (code "191") (name "unconnected-(U1C-GPMC_AD12-PadP6)") (class "Default")
      (node (ref "U1") (pin "P6") (pinfunction "GPMC_AD12_P6") (pintype "bidirectional"))
    )
    (net (code "192") (name "unconnected-(U1C-GPMC_AD13-PadR6)") (class "Default")
      (node (ref "U1") (pin "R6") (pinfunction "GPMC_AD13_R6") (pintype "bidirectional"))
    )
    (net (code "193") (name "unconnected-(U1C-GPMC_AD14-PadT6)") (class "Default")
      (node (ref "U1") (pin "T6") (pinfunction "GPMC_AD14_T6") (pintype "bidirectional"))
    )
    (net (code "194") (name "unconnected-(U1C-GPMC_AD15-PadP7)") (class "Default")
      (node (ref "U1") (pin "P7") (pinfunction "GPMC_AD15_P7") (pintype "bidirectional"))
    )
    (net (code "195") (name "unconnected-(U1C-GPMC_ADVN_ALE-PadM1)") (class "Default")
      (node (ref "U1") (pin "M1") (pinfunction "GPMC_ADVN_ALE_M1") (pintype "bidirectional"))
    )
    (net (code "196") (name "unconnected-(U1C-GPMC_BEN0_CLE-PadN3)") (class "Default")
      (node (ref "U1") (pin "N3") (pinfunction "GPMC_BEN0_CLE_N3") (pintype "bidirectional"))
    )
    (net (code "197") (name "unconnected-(U1C-GPMC_BEN1-PadN14)") (class "Default")
      (node (ref "U1") (pin "N14") (pinfunction "GPMC_BEN1_N14") (pintype "bidirectional"))
    )
    (net (code "198") (name "unconnected-(U1C-GPMC_CLK-PadT7)") (class "Default")
      (node (ref "U1") (pin "T7") (pinfunction "GPMC_CLK_T7") (pintype "bidirectional"))
    )
    (net (code "199") (name "unconnected-(U1C-GPMC_CSN0-PadP3)") (class "Default")
      (node (ref "U1") (pin "P3") (pinfunction "GPMC_CSN0_P3") (pintype "bidirectional"))
    )
    (net (code "200") (name "unconnected-(U1C-GPMC_CSN1-PadP2)") (class "Default")
      (node (ref "U1") (pin "P2") (pinfunction "GPMC_CSN1_P2") (pintype "bidirectional"))
    )
    (net (code "201") (name "unconnected-(U1C-GPMC_CSN2-PadP1)") (class "Default")
      (node (ref "U1") (pin "P1") (pinfunction "GPMC_CSN2_P1") (pintype "bidirectional"))
    )
    (net (code "202") (name "unconnected-(U1C-GPMC_CSN3-PadR7)") (class "Default")
      (node (ref "U1") (pin "R7") (pinfunction "GPMC_CSN3_R7") (pintype "bidirectional"))
    )
    (net (code "203") (name "unconnected-(U1C-GPMC_OEN_REN-PadN1)") (class "Default")
      (node (ref "U1") (pin "N1") (pinfunction "GPMC_OEN_REN_N1") (pintype "bidirectional"))
    )
    (net (code "204") (name "unconnected-(U1C-GPMC_WAIT0-PadP15)") (class "Default")
      (node (ref "U1") (pin "P15") (pinfunction "GPMC_WAIT0_P15") (pintype "bidirectional"))
    )
    (net (code "205") (name "unconnected-(U1C-GPMC_WEN-PadN2)") (class "Default")
      (node (ref "U1") (pin "N2") (pinfunction "GPMC_WEN_N2") (pintype "bidirectional"))
    )
    (net (code "206") (name "unconnected-(U1C-GPMC_WPN-PadR16)") (class "Default")
      (node (ref "U1") (pin "R16") (pinfunction "GPMC_WPN_R16") (pintype "bidirectional"))
    )
    (net (code "207") (name "unconnected-(U1C-MCASP0_ACLKR-PadA3)") (class "Default")
      (node (ref "U1") (pin "A3") (pinfunction "MCASP0_ACLKR_A3") (pintype "bidirectional"))
    )
    (net (code "208") (name "unconnected-(U1C-MCASP0_ACLKX-PadA1)") (class "Default")
      (node (ref "U1") (pin "A1") (pinfunction "MCASP0_ACLKX_A1") (pintype "bidirectional"))
    )
    (net (code "209") (name "unconnected-(U1C-MCASP0_AHCLKR-PadB1)") (class "Default")
      (node (ref "U1") (pin "B1") (pinfunction "MCASP0_AHCLKR_B1") (pintype "bidirectional"))
    )
    (net (code "210") (name "unconnected-(U1C-MCASP0_AHCLKX-PadC4)") (class "Default")
      (node (ref "U1") (pin "C4") (pinfunction "MCASP0_AHCLKX_C4") (pintype "bidirectional"))
    )
    (net (code "211") (name "unconnected-(U1C-MCASP0_AXR0-PadB2)") (class "Default")
      (node (ref "U1") (pin "B2") (pinfunction "MCASP0_AXR0_B2") (pintype "bidirectional"))
    )
    (net (code "212") (name "unconnected-(U1C-MCASP0_AXR1-PadC3)") (class "Default")
      (node (ref "U1") (pin "C3") (pinfunction "MCASP0_AXR1_C3") (pintype "bidirectional"))
    )
    (net (code "213") (name "unconnected-(U1C-MCASP0_FSR-PadB3)") (class "Default")
      (node (ref "U1") (pin "B3") (pinfunction "MCASP0_FSR_B3") (pintype "bidirectional"))
    )
    (net (code "214") (name "unconnected-(U1C-MCASP0_FSX-PadA2)") (class "Default")
      (node (ref "U1") (pin "A2") (pinfunction "MCASP0_FSX_A2") (pintype "bidirectional"))
    )
    (net (code "215") (name "unconnected-(U1C-MMC0_CLK-PadB15)") (class "Default")
      (node (ref "U1") (pin "B15") (pinfunction "MMC0_CLK_B15") (pintype "bidirectional"))
    )
    (net (code "216") (name "unconnected-(U1C-MMC0_CMD-PadB16)") (class "Default")
      (node (ref "U1") (pin "B16") (pinfunction "MMC0_CMD_B16") (pintype "bidirectional"))
    )
    (net (code "217") (name "unconnected-(U1C-MMC0_DAT0-PadA16)") (class "Default")
      (node (ref "U1") (pin "A16") (pinfunction "MMC0_DAT0_A16") (pintype "bidirectional"))
    )
    (net (code "218") (name "unconnected-(U1C-MMC0_DAT1-PadA15)") (class "Default")
      (node (ref "U1") (pin "A15") (pinfunction "MMC0_DAT1_A15") (pintype "bidirectional"))
    )
    (net (code "219") (name "unconnected-(U1C-MMC0_DAT2-PadC16)") (class "Default")
      (node (ref "U1") (pin "C16") (pinfunction "MMC0_DAT2_C16") (pintype "bidirectional"))
    )
    (net (code "220") (name "unconnected-(U1C-MMC0_DAT3-PadC15)") (class "Default")
      (node (ref "U1") (pin "C15") (pinfunction "MMC0_DAT3_C15") (pintype "bidirectional"))
    )
    (net (code "221") (name "unconnected-(U1C-SPI0_CS0-PadA14)") (class "Default")
      (node (ref "U1") (pin "A14") (pinfunction "SPI0_CS0_A14") (pintype "bidirectional"))
    )
    (net (code "222") (name "unconnected-(U1C-SPI0_CS1-PadC14)") (class "Default")
      (node (ref "U1") (pin "C14") (pinfunction "SPI0_CS1_C14") (pintype "bidirectional"))
    )
    (net (code "223") (name "unconnected-(U1C-SPI0_D0-PadB13)") (class "Default")
      (node (ref "U1") (pin "B13") (pinfunction "SPI0_D0_B13") (pintype "bidirectional"))
    )
    (net (code "224") (name "unconnected-(U1C-SPI0_D1-PadB14)") (class "Default")
      (node (ref "U1") (pin "B14") (pinfunction "SPI0_D1_B14") (pintype "bidirectional"))
    )
    (net (code "225") (name "unconnected-(U1C-SPI0_SCLK-PadA13)") (class "Default")
      (node (ref "U1") (pin "A13") (pinfunction "SPI0_SCLK_A13") (pintype "bidirectional"))
    )
    (net (code "226") (name "unconnected-(U1C-UART0_CTSN-PadC12)") (class "Default")
      (node (ref "U1") (pin "C12") (pinfunction "UART0_CTSN_C12") (pintype "bidirectional"))
    )
    (net (code "227") (name "unconnected-(U1C-UART0_RTSN-PadC13)") (class "Default")
      (node (ref "U1") (pin "C13") (pinfunction "UART0_RTSN_C13") (pintype "bidirectional"))
    )
    (net (code "228") (name "unconnected-(U1C-UART0_RXD-PadA12)") (class "Default")
      (node (ref "U1") (pin "A12") (pinfunction "UART0_RXD_A12") (pintype "bidirectional"))
    )
    (net (code "229") (name "unconnected-(U1C-UART0_TXD-PadB12)") (class "Default")
      (node (ref "U1") (pin "B12") (pinfunction "UART0_TXD_B12") (pintype "bidirectional"))
    )
    (net (code "230") (name "unconnected-(U1C-UART1_CTSN-PadB10)") (class "Default")
      (node (ref "U1") (pin "B10") (pinfunction "UART1_CTSN_B10") (pintype "bidirectional"))
    )
    (net (code "231") (name "unconnected-(U1C-UART1_RTSN-PadA10)") (class "Default")
      (node (ref "U1") (pin "A10") (pinfunction "UART1_RTSN_A10") (pintype "bidirectional"))
    )
    (net (code "232") (name "unconnected-(U1C-UART1_RXD-PadA11)") (class "Default")
      (node (ref "U1") (pin "A11") (pinfunction "UART1_RXD_A11") (pintype "bidirectional"))
    )
    (net (code "233") (name "unconnected-(U1C-UART1_TXD-PadB11)") (class "Default")
      (node (ref "U1") (pin "B11") (pinfunction "UART1_TXD_B11") (pintype "bidirectional"))
    )
    (net (code "234") (name "unconnected-(U1C-XDMA_EVENT_INTR0-PadA4)") (class "Default")
      (node (ref "U1") (pin "A4") (pinfunction "XDMA_EVENT_INTR0_A4") (pintype "bidirectional"))
    )
    (net (code "235") (name "unconnected-(U1C-XDMA_EVENT_INTR1-PadB4)") (class "Default")
      (node (ref "U1") (pin "B4") (pinfunction "XDMA_EVENT_INTR1_B4") (pintype "bidirectional"))
    )
    (net (code "236") (name "unconnected-(U1F-CAP_VDD_RTC-PadD5)") (class "Default")
      (node (ref "U1") (pin "D5") (pinfunction "CAP_VDD_RTC_D5") (pintype "bidirectional"))
    )
    (net (code "237") (name "unconnected-(U1F-NC-PadD12)") (class "Default")
      (node (ref "U1") (pin "D12") (pinfunction "NC_D12") (pintype "bidirectional"))
    )
    (net (code "238") (name "unconnected-(U1F-NC-PadJ6)") (class "Default")
      (node (ref "U1") (pin "J6") (pinfunction "NC_J6") (pintype "bidirectional"))
    )
    (net (code "239") (name "unconnected-(U1F-NC-PadK4)") (class "Default")
      (node (ref "U1") (pin "K4") (pinfunction "NC_K4") (pintype "bidirectional"))
    )
    (net (code "240") (name "unconnected-(U1F-VPP-PadH6)") (class "Default")
      (node (ref "U1") (pin "H6") (pinfunction "VPP_H6") (pintype "bidirectional"))
    )
    (net (code "241") (name "~{FAULT}") (class "Default")
      (node (ref "Q6") (pin "3") (pinfunction "D_3") (pintype "passive"))
      (node (ref "R38") (pin "1") (pinfunction "1_1") (pintype "passive"))
      (node (ref "TP8") (pin "1") (pinfunction "1_1") (pintype "passive"))
      (node (ref "U3") (pin "7") (pinfunction "IO2_7") (pintype "bidirectional"))
    )
    (net (code "242") (name "~{SHUTDOWN}") (class "Default")
      (node (ref "J6") (pin "39") (pinfunction "39_39") (pintype "passive"))
      (node (ref "J6") (pin "40") (pinfunction "40_40") (pintype "passive"))
      (node (ref "JP1") (pin "3") (pinfunction "3_3") (pintype "passive"))
      (node (ref "JP10") (pin "10") (pinfunction "10_10") (pintype "passive"))
      (node (ref "JP10") (pin "9") (pinfunction "9_9") (pintype "passive"))
    )
  )
)
